# base-32-bit.net
KiCad netlist of a schematic drawn in Altium Designer
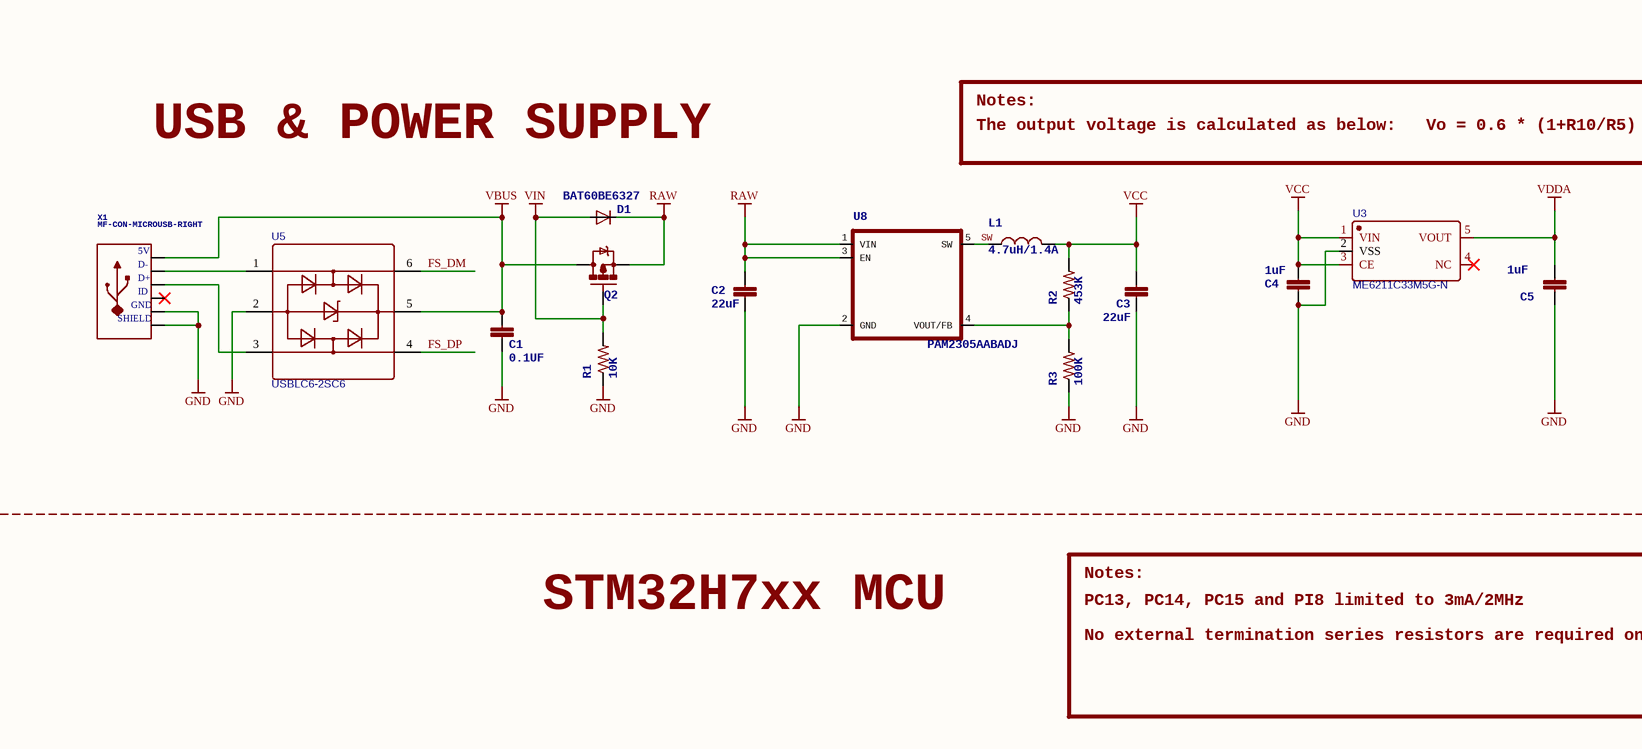
[diagram p0: base-32-bit.SchDoc, top left]
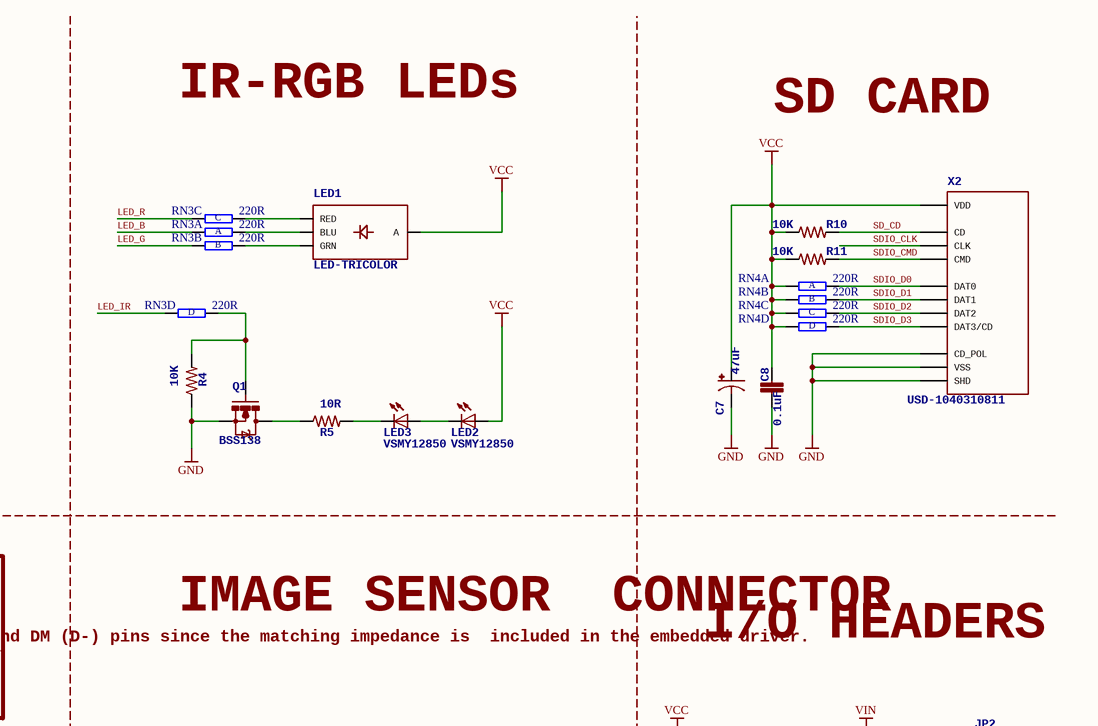
[diagram p1: base-32-bit.SchDoc, top right]
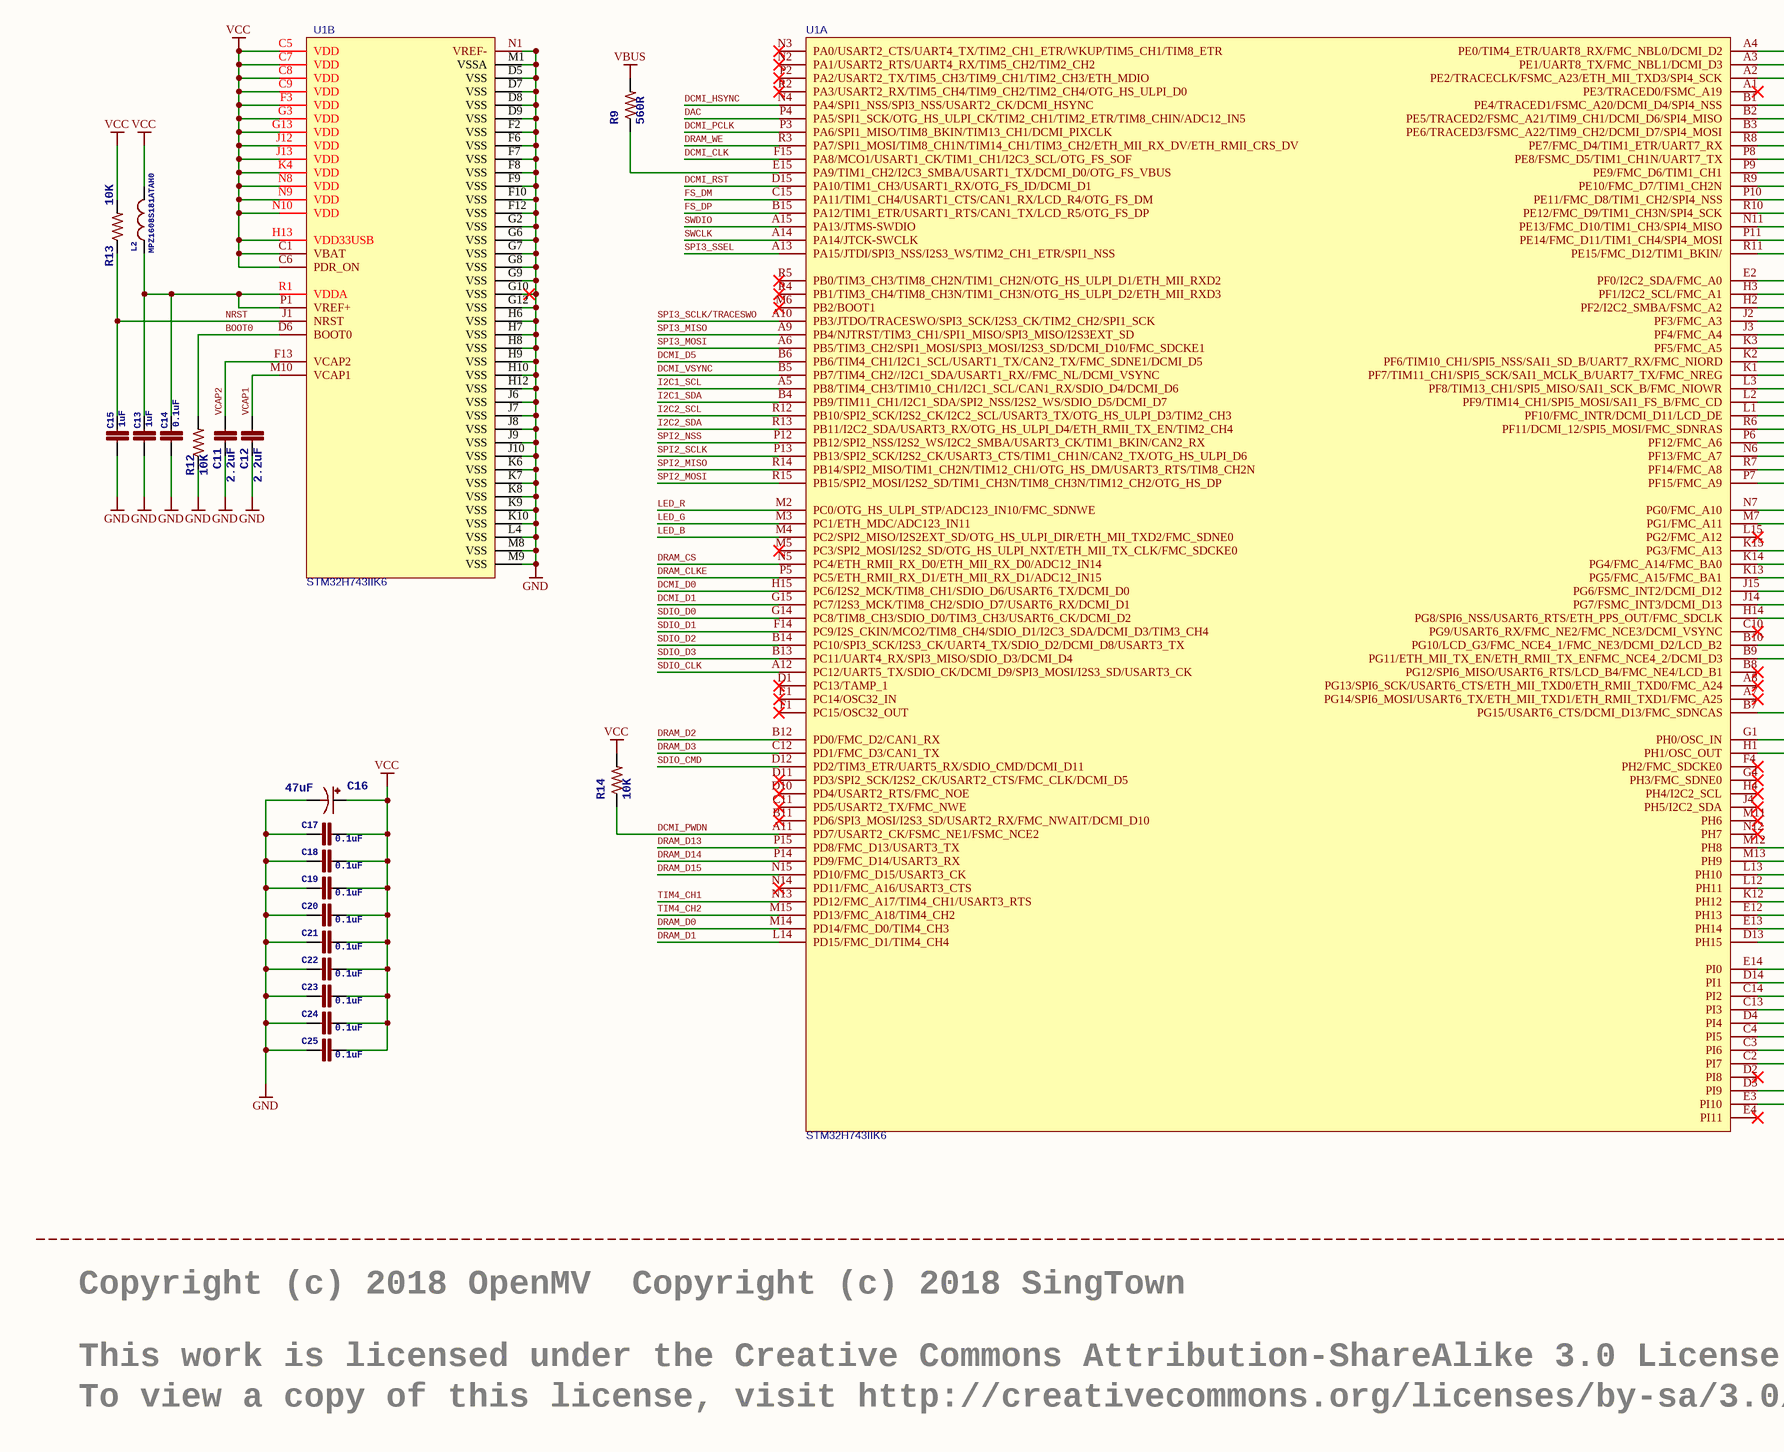
[diagram p2: base-32-bit.SchDoc, bottom left]
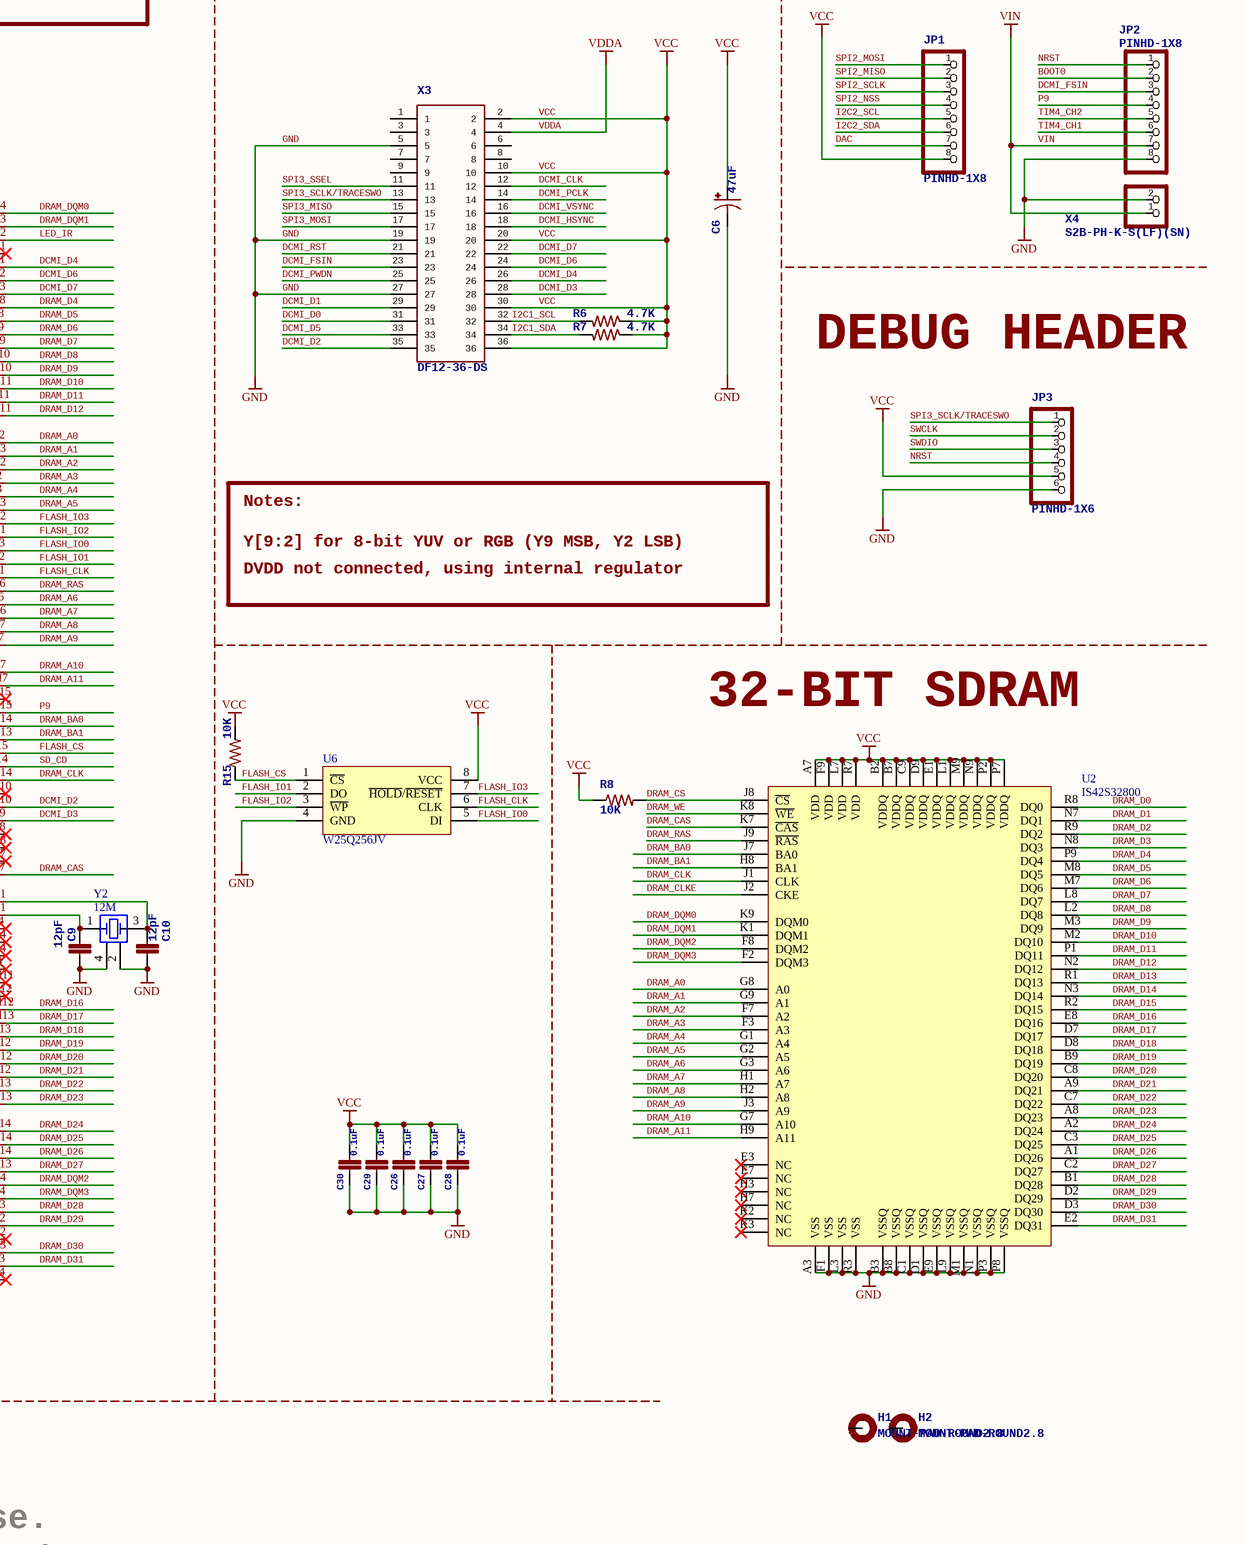
[diagram p3: base-32-bit.SchDoc, bottom right]

(export (version "E")
  (design (tool "Eeschema 10.0.6"))
  (components
    (comp (ref "C1")
      (value "0.1UF")
      (footprint "C0603")
      (description "CapacitorStandard 0603 ceramic capacitor, and 0.1\" leaded capacitor.")
      (libsource (lib "sfe") (part "CAP0805"))
    )
    (comp (ref "C2")
      (value "22uF")
      (footprint "0805")
      (description "CapacitorStandard 0603 ceramic capacitor, and 0.1\" leaded capacitor.")
      (libsource (lib "sfe") (part "CAP0805"))
    )
    (comp (ref "C3")
      (value "22uF")
      (footprint "0805")
      (description "CapacitorStandard 0603 ceramic capacitor, and 0.1\" leaded capacitor.")
      (libsource (lib "sfe") (part "CAP0805"))
    )
    (comp (ref "C4")
      (value "1uF")
      (footprint "0805")
      (description "CapacitorStandard 0603 ceramic capacitor, and 0.1\" leaded capacitor.")
      (libsource (lib "sfe") (part "CAP0805"))
    )
    (comp (ref "C5")
      (value "1uF")
      (footprint "0805")
      (description "CapacitorStandard 0603 ceramic capacitor, and 0.1\" leaded capacitor.")
      (libsource (lib "sfe") (part "CAP0805"))
    )
    (comp (ref "C6") (value "47uF") (footprint "EIA3216") (libsource (lib "sfe") (part "CAP_POL1206")))
    (comp (ref "C7") (value "47uF") (footprint "EIA3216") (libsource (lib "sfe") (part "CAP_POL1206")))
    (comp (ref "C8")
      (value "0.1uF")
      (footprint "0603-CAP")
      (description "CapacitorStandard 0603 ceramic capacitor, and 0.1\" leaded capacitor.")
      (libsource (lib "") (part "CAP0603-CAP_1"))
    )
    (comp (ref "C9")
      (value "12pF")
      (footprint "0603-CAP")
      (description "CapacitorStandard 0603 ceramic capacitor, and 0.1\" leaded capacitor.")
      (libsource (lib "sfe") (part "CAP0603-CAP"))
    )
    (comp (ref "C10")
      (value "12pF")
      (footprint "0603-CAP")
      (description "CapacitorStandard 0603 ceramic capacitor, and 0.1\" leaded capacitor.")
      (libsource (lib "sfe") (part "CAP0603-CAP"))
    )
    (comp (ref "C11")
      (value "2.2uF")
      (footprint "C0402")
      (description "CapacitorStandard 0603 ceramic capacitor, and 0.1\" leaded capacitor.")
      (libsource (lib "") (part "CAP0603-CAP_1"))
    )
    (comp (ref "C12")
      (value "2.2uF")
      (footprint "C0402")
      (description "CapacitorStandard 0603 ceramic capacitor, and 0.1\" leaded capacitor.")
      (libsource (lib "") (part "CAP0603-CAP_1"))
    )
    (comp (ref "C13")
      (value "1uF")
      (footprint "C0402")
      (description "CapacitorStandard 0603 ceramic capacitor, and 0.1\" leaded capacitor.")
      (libsource (lib "") (part "CAP0402-CAP_1"))
    )
    (comp (ref "C14")
      (value "0.1uF")
      (footprint "C0402")
      (description "CapacitorStandard 0603 ceramic capacitor, and 0.1\" leaded capacitor.")
      (libsource (lib "") (part "CAP0402-CAP_1"))
    )
    (comp (ref "C15")
      (value "1uF")
      (footprint "C0402")
      (description "CapacitorStandard 0603 ceramic capacitor, and 0.1\" leaded capacitor.")
      (libsource (lib "") (part "CAP0402-CAP_1"))
    )
    (comp (ref "C16") (value "47uF") (footprint "EIA3216") (libsource (lib "") (part "CAP_POL1206_1")))
    (comp (ref "C17")
      (value "0.1uF")
      (footprint "C0402")
      (description "CapacitorStandard 0603 ceramic capacitor, and 0.1\" leaded capacitor.")
      (libsource (lib "sfe") (part "CAP0402-CAP"))
    )
    (comp (ref "C18")
      (value "0.1uF")
      (footprint "C0402")
      (description "CapacitorStandard 0603 ceramic capacitor, and 0.1\" leaded capacitor.")
      (libsource (lib "sfe") (part "CAP0402-CAP"))
    )
    (comp (ref "C19")
      (value "0.1uF")
      (footprint "C0402")
      (description "CapacitorStandard 0603 ceramic capacitor, and 0.1\" leaded capacitor.")
      (libsource (lib "sfe") (part "CAP0402-CAP"))
    )
    (comp (ref "C20")
      (value "0.1uF")
      (footprint "C0402")
      (description "CapacitorStandard 0603 ceramic capacitor, and 0.1\" leaded capacitor.")
      (libsource (lib "sfe") (part "CAP0402-CAP"))
    )
    (comp (ref "C21")
      (value "0.1uF")
      (footprint "C0402")
      (description "CapacitorStandard 0603 ceramic capacitor, and 0.1\" leaded capacitor.")
      (libsource (lib "sfe") (part "CAP0402-CAP"))
    )
    (comp (ref "C22")
      (value "0.1uF")
      (footprint "C0402")
      (description "CapacitorStandard 0603 ceramic capacitor, and 0.1\" leaded capacitor.")
      (libsource (lib "sfe") (part "CAP0402-CAP"))
    )
    (comp (ref "C23")
      (value "0.1uF")
      (footprint "C0402")
      (description "CapacitorStandard 0603 ceramic capacitor, and 0.1\" leaded capacitor.")
      (libsource (lib "sfe") (part "CAP0402-CAP"))
    )
    (comp (ref "C24")
      (value "0.1uF")
      (footprint "C0402")
      (description "CapacitorStandard 0603 ceramic capacitor, and 0.1\" leaded capacitor.")
      (libsource (lib "sfe") (part "CAP0402-CAP"))
    )
    (comp (ref "C25")
      (value "0.1uF")
      (footprint "C0402")
      (description "CapacitorStandard 0603 ceramic capacitor, and 0.1\" leaded capacitor.")
      (libsource (lib "sfe") (part "CAP0402-CAP"))
    )
    (comp (ref "C26")
      (value "0.1uF")
      (footprint "C0402")
      (description "CapacitorStandard 0603 ceramic capacitor, and 0.1\" leaded capacitor.")
      (libsource (lib "") (part "CAP0402-CAP_1"))
    )
    (comp (ref "C27")
      (value "0.1uF")
      (footprint "C0402")
      (description "CapacitorStandard 0603 ceramic capacitor, and 0.1\" leaded capacitor.")
      (libsource (lib "") (part "CAP0402-CAP_1"))
    )
    (comp (ref "C28")
      (value "0.1uF")
      (footprint "C0402")
      (description "CapacitorStandard 0603 ceramic capacitor, and 0.1\" leaded capacitor.")
      (libsource (lib "") (part "CAP0402-CAP_1"))
    )
    (comp (ref "C29")
      (value "0.1uF")
      (footprint "C0402")
      (description "CapacitorStandard 0603 ceramic capacitor, and 0.1\" leaded capacitor.")
      (libsource (lib "") (part "CAP0402-CAP_1"))
    )
    (comp (ref "C30")
      (value "0.1uF")
      (footprint "C0402")
      (description "CapacitorStandard 0603 ceramic capacitor, and 0.1\" leaded capacitor.")
      (libsource (lib "") (part "CAP0402-CAP_1"))
    )
    (comp (ref "D1") (value "BAT60BE6327") (footprint "SOD-323") (libsource (lib "sfe") (part "DIODESOD")))
    (comp (ref "H1")
      (value "MOUNT-PAD-ROUND2.8")
      (footprint "2,8-PAD")
      (description "MOUNTING PAD, round")
      (libsource (lib "holes") (part "MOUNT-PAD-ROUND2.8"))
    )
    (comp (ref "H2")
      (value "MOUNT-PAD-ROUND2.8")
      (footprint "2,8-PAD")
      (description "MOUNTING PAD, round")
      (libsource (lib "holes") (part "MOUNT-PAD-ROUND2.8"))
    )
    (comp (ref "JP1")
      (value "PINHD-1X8")
      (footprint "1X08")
      (description "PIN HEADER")
      (libsource (lib "pinhead") (part "PINHD-1X8"))
    )
    (comp (ref "JP2")
      (value "PINHD-1X8")
      (footprint "1X08")
      (description "PIN HEADER")
      (libsource (lib "pinhead") (part "PINHD-1X8"))
    )
    (comp (ref "JP3")
      (value "PINHD-1X6")
      (footprint "1X06")
      (description "PIN HEADER")
      (libsource (lib "pinhead") (part "PINHD-1X6"))
    )
    (comp (ref "L1") (value "4.7uH/1.4A") (footprint "1007") (libsource (lib "sfe") (part "INDUCTOR1007")))
    (comp (ref "L2")
      (value "MPZ1608S181ATAH0")
      (footprint "0603")
      (libsource (lib "sfe") (part "INDUCTOR0603"))
    )
    (comp (ref "LED1")
      (value "LED-TRICOLOR")
      (footprint "LED-TRICOLOR-SMD")
      (libsource (lib "sfe") (part "LED-TRICOLOR"))
    )
    (comp (ref "LED2") (value "VSMY12850") (footprint "LED-1206") (libsource (lib "sfe") (part "LED1206")))
    (comp (ref "LED3") (value "VSMY12850") (footprint "LED-1206") (libsource (lib "sfe") (part "LED1206")))
    (comp (ref "Q1")
      (value "BSS138")
      (footprint "SOT23-3")
      (libsource (lib "sfe") (part "MOSFET-NCHANNELSMD"))
    )
    (comp (ref "Q2")
      (value "Si2301BDS")
      (footprint "SOT23-3")
      (libsource (lib "sfe") (part "MOSFET-PCHANNELSMD"))
    )
    (comp (ref "R1")
      (value "10K")
      (footprint "R0603")
      (description "ResistorBasic schematic elements and footprints for 0603, 1206, and PTH resistors.")
      (libsource (lib "sfe") (part "RESISTOR0603-RES"))
    )
    (comp (ref "R2")
      (value "453K")
      (footprint "R0603")
      (description "ResistorBasic schematic elements and footprints for 0603, 1206, and PTH resistors.")
      (libsource (lib "sfe") (part "RESISTOR0603-RES"))
    )
    (comp (ref "R3")
      (value "100K")
      (footprint "R0603")
      (description "ResistorBasic schematic elements and footprints for 0603, 1206, and PTH resistors.")
      (libsource (lib "sfe") (part "RESISTOR0603-RES"))
    )
    (comp (ref "R4")
      (value "10K")
      (footprint "R0603")
      (description "ResistorBasic schematic elements and footprints for 0603, 1206, and PTH resistors.")
      (libsource (lib "sfe") (part "RESISTOR0603-RES"))
    )
    (comp (ref "R5")
      (value "10R")
      (footprint "R0603")
      (description "ResistorBasic schematic elements and footprints for 0603, 1206, and PTH resistors.")
      (libsource (lib "sfe") (part "RESISTOR0603-RES"))
    )
    (comp (ref "R6")
      (value "4.7K")
      (footprint "R0603")
      (description "ResistorBasic schematic elements and footprints for 0603, 1206, and PTH resistors.")
      (libsource (lib "sfe") (part "RESISTOR0603-RES"))
    )
    (comp (ref "R7")
      (value "4.7K")
      (footprint "R0603")
      (description "ResistorBasic schematic elements and footprints for 0603, 1206, and PTH resistors.")
      (libsource (lib "sfe") (part "RESISTOR0603-RES"))
    )
    (comp (ref "R8")
      (value "10K")
      (footprint "R0402")
      (description "ResistorBasic schematic elements and footprints for 0603, 1206, and PTH resistors.")
      (libsource (lib "sfe") (part "RESISTOR0402-RES"))
    )
    (comp (ref "R9")
      (value "560R")
      (footprint "R0603")
      (description "ResistorBasic schematic elements and footprints for 0603, 1206, and PTH resistors.")
      (libsource (lib "sfe") (part "RESISTOR0603-RES"))
    )
    (comp (ref "R10")
      (value "10K")
      (footprint "R0603")
      (description "ResistorBasic schematic elements and footprints for 0603, 1206, and PTH resistors.")
      (libsource (lib "sfe") (part "RESISTOR0603-RES"))
    )
    (comp (ref "R11")
      (value "10K")
      (footprint "R0603")
      (description "ResistorBasic schematic elements and footprints for 0603, 1206, and PTH resistors.")
      (libsource (lib "sfe") (part "RESISTOR0603-RES"))
    )
    (comp (ref "R12")
      (value "10K")
      (footprint "R0603")
      (description "ResistorBasic schematic elements and footprints for 0603, 1206, and PTH resistors.")
      (libsource (lib "sfe") (part "RESISTOR0603-RES"))
    )
    (comp (ref "R13")
      (value "10K")
      (footprint "R0402")
      (description "ResistorBasic schematic elements and footprints for 0603, 1206, and PTH resistors.")
      (libsource (lib "sfe") (part "RESISTOR0603-RES"))
    )
    (comp (ref "R14")
      (value "10K")
      (footprint "R0603")
      (description "ResistorBasic schematic elements and footprints for 0603, 1206, and PTH resistors.")
      (libsource (lib "sfe") (part "RESISTOR0603-RES"))
    )
    (comp (ref "R15")
      (value "10K")
      (footprint "R0603")
      (description "ResistorBasic schematic elements and footprints for 0603, 1206, and PTH resistors.")
      (libsource (lib "sfe") (part "RESISTOR0402-RES"))
    )
    (comp (ref "RN3")
      (value "220R")
      (footprint "RCA-8P4R-0402")
      (libsource (lib "Integrated_Library1") (part "排阻_4P"))
    )
    (comp (ref "RN4")
      (value "220R")
      (footprint "RCA-8P4R-0402")
      (libsource (lib "Integrated_Library1") (part "排阻_4P"))
    )
    (comp (ref "U1")
      (value "STM32H743IIK6")
      (footprint "UFBGA-201_L10.0-W10.0-P0.65-TL_STM32H743IIK6")
      (fields
        (field (name "BOM_SUPPLIER PART") "C129442")
        (field (name "SUBPART_NO") "2")
        (field (name "CONTRIBUTOR") "LCSC")
      )
      (libsource (lib "Integrated_Library1") (part "STM32H743IIK6"))
    )
    (comp (ref "U2")
      (value "IS42S32800")
      (footprint "BGA-90-8000X13000DE")
      (libsource (lib "Schlib1") (part "IS42S32800"))
    )
    (comp (ref "U3")
      (value "ME6211C33M5G-N")
      (footprint "SOT-23-5")
      (fields (field (name "BOM_SUPPLIER PART") "C82942"))
      (libsource (lib "Integrated_Library1") (part "ME6211C33M5G-N"))
    )
    (comp (ref "U5")
      (value "USBLC6-2SC6")
      (footprint "SOT-23-6")
      (fields (field (name "BOM_SUPPLIER PART") "C7519"))
      (libsource (lib "Integrated_Library1") (part "USBLC6-2SC6"))
    )
    (comp (ref "U6")
      (value "W25Q256JV")
      (footprint "WSON-8_L8.0-W6.10-P1.27-BL-EP")
      (libsource (lib "Integrated_Library1") (part "W25Q128JVSQ"))
    )
    (comp (ref "U8")
      (value "PAM2305AABADJ")
      (footprint "TSOT25")
      (libsource (lib "regulators") (part "PAM2305AAB330"))
    )
    (comp (ref "X1")
      (value "MF-CON-MICROUSB-RIGHT")
      (footprint "MICROUSB-RIGHT")
      (libsource (lib "base-16-bit") (part "USB_MICRO_RIGHT"))
    )
    (comp (ref "X2")
      (value "USD-1040310811")
      (footprint "1040310811")
      (libsource (lib "base-16-bit") (part "USD-1040310811"))
    )
    (comp (ref "X3")
      (value "DF12-36-DS")
      (footprint "DF12-36-DS")
      (libsource (lib "DF12") (part "DF12-36-DS"))
    )
    (comp (ref "X4")
      (value "S2B-PH-K-S(LF)(SN)")
      (footprint "JST-PH-2-THM-RA")
      (libsource (lib "adafruit-updated") (part "JST_2PIN-THM-RA"))
    )
    (comp (ref "Y2")
      (value "12M")
      (footprint "OSC-SMD_4P-L2.5-W2.0-BL")
      (libsource (lib "wwwmcucn_sch") (part "XTAL-NV-4"))
    )
  )
  (nets
    (net (code "1") (name "/BOOT0") (class "Default")
      (node (ref "JP2") (pin "2") (pinfunction "2_2") (pintype "passive"))
      (node (ref "R12") (pin "2") (pinfunction "2_2") (pintype "passive"))
      (node (ref "U1") (pin "D6") (pinfunction "BOOT0_D6") (pintype "passive"))
    )
    (net (code "2") (name "/DAC") (class "Default")
      (node (ref "JP1") (pin "7") (pinfunction "7_7") (pintype "passive"))
      (node (ref "U1") (pin "P4") (pinfunction "PA5/SPI1_SCK/OTG_HS_ULPI_CK/TIM2_CH1/TIM2_ETR/TIM8_CHIN/ADC12_IN5_P4") (pintype "passive"))
    )
    (net (code "3") (name "/DCMI_CLK") (class "Default")
      (node (ref "U1") (pin "F15") (pinfunction "PA8/MCO1/USART1_CK/TIM1_CH1/I2C3_SCL/OTG_FS_SOF_F15") (pintype "passive"))
      (node (ref "X3") (pin "12") (pinfunction "12_12") (pintype "passive"))
    )
    (net (code "4") (name "/DCMI_D0") (class "Default")
      (node (ref "U1") (pin "H15") (pinfunction "PC6/I2S2_MCK/TIM8_CH1/SDIO_D6/USART6_TX/DCMI_D0_H15") (pintype "passive"))
      (node (ref "X3") (pin "31") (pinfunction "31_31") (pintype "passive"))
    )
    (net (code "5") (name "/DCMI_D1") (class "Default")
      (node (ref "U1") (pin "G15") (pinfunction "PC7/I2S3_MCK/TIM8_CH2/SDIO_D7/USART6_RX/DCMI_D1_G15") (pintype "passive"))
      (node (ref "X3") (pin "29") (pinfunction "29_29") (pintype "passive"))
    )
    (net (code "6") (name "/DCMI_D2") (class "Default")
      (node (ref "U1") (pin "B10") (pinfunction "PG10/LCD_G3/FMC_NCE4_1/FMC_NE3/DCMI_D2/LCD_B2_B10") (pintype "passive"))
      (node (ref "X3") (pin "35") (pinfunction "35_35") (pintype "passive"))
    )
    (net (code "7") (name "/DCMI_D3") (class "Default")
      (node (ref "U1") (pin "B9") (pinfunction "PG11/ETH_MII_TX_EN/ETH_RMII_TX_ENFMC_NCE4_2/DCMI_D3_B9") (pintype "passive"))
      (node (ref "X3") (pin "28") (pinfunction "28_28") (pintype "passive"))
    )
    (net (code "8") (name "/DCMI_D4") (class "Default")
      (node (ref "U1") (pin "B1") (pinfunction "PE4/TRACED1/FSMC_A20/DCMI_D4/SPI4_NSS_B1") (pintype "passive"))
      (node (ref "X3") (pin "26") (pinfunction "26_26") (pintype "passive"))
    )
    (net (code "9") (name "/DCMI_D5") (class "Default")
      (node (ref "U1") (pin "B6") (pinfunction "PB6/TIM4_CH1/I2C1_SCL/USART1_TX/CAN2_TX/FMC_SDNE1/DCMI_D5_B6") (pintype "passive"))
      (node (ref "X3") (pin "33") (pinfunction "33_33") (pintype "passive"))
    )
    (net (code "10") (name "/DCMI_D6") (class "Default")
      (node (ref "U1") (pin "B2") (pinfunction "PE5/TRACED2/FSMC_A21/TIM9_CH1/DCMI_D6/SPI4_MISO_B2") (pintype "passive"))
      (node (ref "X3") (pin "24") (pinfunction "24_24") (pintype "passive"))
    )
    (net (code "11") (name "/DCMI_D7") (class "Default")
      (node (ref "U1") (pin "B3") (pinfunction "PE6/TRACED3/FSMC_A22/TIM9_CH2/DCMI_D7/SPI4_MOSI_B3") (pintype "passive"))
      (node (ref "X3") (pin "22") (pinfunction "22_22") (pintype "passive"))
    )
    (net (code "12") (name "/DCMI_FSIN") (class "Default")
      (node (ref "JP2") (pin "3") (pinfunction "3_3") (pintype "passive"))
      (node (ref "X3") (pin "23") (pinfunction "23_23") (pintype "passive"))
    )
    (net (code "13") (name "/DCMI_HSYNC") (class "Default")
      (node (ref "U1") (pin "N4") (pinfunction "PA4/SPI1_NSS/SPI3_NSS/USART2_CK/DCMI_HSYNC_N4") (pintype "passive"))
      (node (ref "X3") (pin "18") (pinfunction "18_18") (pintype "passive"))
    )
    (net (code "14") (name "/DCMI_PCLK") (class "Default")
      (node (ref "U1") (pin "P3") (pinfunction "PA6/SPI1_MISO/TIM8_BKIN/TIM13_CH1/DCMI_PIXCLK_P3") (pintype "passive"))
      (node (ref "X3") (pin "14") (pinfunction "14_14") (pintype "passive"))
    )
    (net (code "15") (name "/DCMI_PWDN") (class "Default")
      (node (ref "R14") (pin "1") (pinfunction "1_1") (pintype "passive"))
      (node (ref "U1") (pin "A11") (pinfunction "PD7/USART2_CK/FSMC_NE1/FSMC_NCE2_A11") (pintype "passive"))
      (node (ref "X3") (pin "25") (pinfunction "25_25") (pintype "passive"))
    )
    (net (code "16") (name "/DCMI_RST") (class "Default")
      (node (ref "U1") (pin "D15") (pinfunction "PA10/TIM1_CH3/USART1_RX/OTG_FS_ID/DCMI_D1_D15") (pintype "passive"))
      (node (ref "X3") (pin "21") (pinfunction "21_21") (pintype "passive"))
    )
    (net (code "17") (name "/DCMI_VSYNC") (class "Default")
      (node (ref "U1") (pin "B5") (pinfunction "PB7/TIM4_CH2//I2C1_SDA/USART1_RX//FMC_NL/DCMI_VSYNC_B5") (pintype "passive"))
      (node (ref "X3") (pin "16") (pinfunction "16_16") (pintype "passive"))
    )
    (net (code "18") (name "/DRAM_A0") (class "Default")
      (node (ref "U1") (pin "E2") (pinfunction "PF0/I2C2_SDA/FMC_A0_E2") (pintype "passive"))
      (node (ref "U2") (pin "G8") (pinfunction "A0_G8") (pintype "passive"))
    )
    (net (code "19") (name "/DRAM_A1") (class "Default")
      (node (ref "U1") (pin "H3") (pinfunction "PF1/I2C2_SCL/FMC_A1_H3") (pintype "passive"))
      (node (ref "U2") (pin "G9") (pinfunction "A1_G9") (pintype "passive"))
    )
    (net (code "20") (name "/DRAM_A2") (class "Default")
      (node (ref "U1") (pin "H2") (pinfunction "PF2/I2C2_SMBA/FSMC_A2_H2") (pintype "passive"))
      (node (ref "U2") (pin "F7") (pinfunction "A2_F7") (pintype "passive"))
    )
    (net (code "21") (name "/DRAM_A3") (class "Default")
      (node (ref "U1") (pin "J2") (pinfunction "PF3/FMC_A3_J2") (pintype "passive"))
      (node (ref "U2") (pin "F3") (pinfunction "A3_F3") (pintype "passive"))
    )
    (net (code "22") (name "/DRAM_A4") (class "Default")
      (node (ref "U1") (pin "J3") (pinfunction "PF4/FMC_A4_J3") (pintype "passive"))
      (node (ref "U2") (pin "G1") (pinfunction "A4_G1") (pintype "passive"))
    )
    (net (code "23") (name "/DRAM_A5") (class "Default")
      (node (ref "U1") (pin "K3") (pinfunction "PF5/FMC_A5_K3") (pintype "passive"))
      (node (ref "U2") (pin "G2") (pinfunction "A5_G2") (pintype "passive"))
    )
    (net (code "24") (name "/DRAM_A6") (class "Default")
      (node (ref "U1") (pin "P6") (pinfunction "PF12/FMC_A6_P6") (pintype "passive"))
      (node (ref "U2") (pin "G3") (pinfunction "A6_G3") (pintype "passive"))
    )
    (net (code "25") (name "/DRAM_A7") (class "Default")
      (node (ref "U1") (pin "N6") (pinfunction "PF13/FMC_A7_N6") (pintype "passive"))
      (node (ref "U2") (pin "H1") (pinfunction "A7_H1") (pintype "passive"))
    )
    (net (code "26") (name "/DRAM_A8") (class "Default")
      (node (ref "U1") (pin "R7") (pinfunction "PF14/FMC_A8_R7") (pintype "passive"))
      (node (ref "U2") (pin "H2") (pinfunction "A8_H2") (pintype "passive"))
    )
    (net (code "27") (name "/DRAM_A9") (class "Default")
      (node (ref "U1") (pin "P7") (pinfunction "PF15/FMC_A9_P7") (pintype "passive"))
      (node (ref "U2") (pin "J3") (pinfunction "A9_J3") (pintype "passive"))
    )
    (net (code "28") (name "/DRAM_A10") (class "Default")
      (node (ref "U1") (pin "N7") (pinfunction "PG0/FMC_A10_N7") (pintype "passive"))
      (node (ref "U2") (pin "G7") (pinfunction "A10_G7") (pintype "passive"))
    )
    (net (code "29") (name "/DRAM_A11") (class "Default")
      (node (ref "U1") (pin "M7") (pinfunction "PG1/FMC_A11_M7") (pintype "passive"))
      (node (ref "U2") (pin "H9") (pinfunction "A11_H9") (pintype "passive"))
    )
    (net (code "30") (name "/DRAM_BA0") (class "Default")
      (node (ref "U1") (pin "K14") (pinfunction "PG4/FMC_A14/FMC_BA0_K14") (pintype "passive"))
      (node (ref "U2") (pin "J7") (pinfunction "BA0_J7") (pintype "passive"))
    )
    (net (code "31") (name "/DRAM_BA1") (class "Default")
      (node (ref "U1") (pin "K13") (pinfunction "PG5/FMC_A15/FMC_BA1_K13") (pintype "passive"))
      (node (ref "U2") (pin "H8") (pinfunction "BA1_H8") (pintype "passive"))
    )
    (net (code "32") (name "/DRAM_CAS") (class "Default")
      (node (ref "U1") (pin "B7") (pinfunction "PG15/USART6_CTS/DCMI_D13/FMC_SDNCAS_B7") (pintype "passive"))
      (node (ref "U2") (pin "K7") (pinfunction "~{CAS}_K7") (pintype "passive"))
    )
    (net (code "33") (name "/DRAM_CLK") (class "Default")
      (node (ref "U1") (pin "H14") (pinfunction "PG8/SPI6_NSS/USART6_RTS/ETH_PPS_OUT/FMC_SDCLK_H14") (pintype "passive"))
      (node (ref "U2") (pin "J1") (pinfunction "CLK_J1") (pintype "passive"))
    )
    (net (code "34") (name "/DRAM_CLKE") (class "Default")
      (node (ref "U1") (pin "P5") (pinfunction "PC5/ETH_RMII_RX_D1/ETH_MII_RX_D1/ADC12_IN15_P5") (pintype "passive"))
      (node (ref "U2") (pin "J2") (pinfunction "CKE_J2") (pintype "passive"))
    )
    (net (code "35") (name "/DRAM_CS") (class "Default")
      (node (ref "R8") (pin "2") (pinfunction "2_2") (pintype "passive"))
      (node (ref "U1") (pin "N5") (pinfunction "PC4/ETH_RMII_RX_D0/ETH_MII_RX_D0/ADC12_IN14_N5") (pintype "passive"))
      (node (ref "U2") (pin "J8") (pinfunction "~{CS}_J8") (pintype "passive"))
    )
    (net (code "36") (name "/DRAM_D0") (class "Default")
      (node (ref "U1") (pin "M14") (pinfunction "PD14/FMC_D0/TIM4_CH3_M14") (pintype "passive"))
      (node (ref "U2") (pin "R8") (pinfunction "DQ0_R8") (pintype "passive"))
    )
    (net (code "37") (name "/DRAM_D1") (class "Default")
      (node (ref "U1") (pin "L14") (pinfunction "PD15/FMC_D1/TIM4_CH4_L14") (pintype "passive"))
      (node (ref "U2") (pin "N7") (pinfunction "DQ1_N7") (pintype "passive"))
    )
    (net (code "38") (name "/DRAM_D2") (class "Default")
      (node (ref "U1") (pin "B12") (pinfunction "PD0/FMC_D2/CAN1_RX_B12") (pintype "passive"))
      (node (ref "U2") (pin "R9") (pinfunction "DQ2_R9") (pintype "passive"))
    )
    (net (code "39") (name "/DRAM_D3") (class "Default")
      (node (ref "U1") (pin "C12") (pinfunction "PD1/FMC_D3/CAN1_TX_C12") (pintype "passive"))
      (node (ref "U2") (pin "N8") (pinfunction "DQ3_N8") (pintype "passive"))
    )
    (net (code "40") (name "/DRAM_D4") (class "Default")
      (node (ref "U1") (pin "R8") (pinfunction "PE7/FMC_D4/TIM1_ETR/UART7_RX_R8") (pintype "passive"))
      (node (ref "U2") (pin "P9") (pinfunction "DQ4_P9") (pintype "passive"))
    )
    (net (code "41") (name "/DRAM_D5") (class "Default")
      (node (ref "U1") (pin "P8") (pinfunction "PE8/FSMC_D5/TIM1_CH1N/UART7_TX_P8") (pintype "passive"))
      (node (ref "U2") (pin "M8") (pinfunction "DQ5_M8") (pintype "passive"))
    )
    (net (code "42") (name "/DRAM_D6") (class "Default")
      (node (ref "U1") (pin "P9") (pinfunction "PE9/FMC_D6/TIM1_CH1_P9") (pintype "passive"))
      (node (ref "U2") (pin "M7") (pinfunction "DQ6_M7") (pintype "passive"))
    )
    (net (code "43") (name "/DRAM_D7") (class "Default")
      (node (ref "U1") (pin "R9") (pinfunction "PE10/FMC_D7/TIM1_CH2N_R9") (pintype "passive"))
      (node (ref "U2") (pin "L8") (pinfunction "DQ7_L8") (pintype "passive"))
    )
    (net (code "44") (name "/DRAM_D8") (class "Default")
      (node (ref "U1") (pin "P10") (pinfunction "PE11/FMC_D8/TIM1_CH2/SPI4_NSS_P10") (pintype "passive"))
      (node (ref "U2") (pin "L2") (pinfunction "DQ8_L2") (pintype "passive"))
    )
    (net (code "45") (name "/DRAM_D9") (class "Default")
      (node (ref "U1") (pin "R10") (pinfunction "PE12/FMC_D9/TIM1_CH3N/SPI4_SCK_R10") (pintype "passive"))
      (node (ref "U2") (pin "M3") (pinfunction "DQ9_M3") (pintype "passive"))
    )
    (net (code "46") (name "/DRAM_D10") (class "Default")
      (node (ref "U1") (pin "N11") (pinfunction "PE13/FMC_D10/TIM1_CH3/SPI4_MISO_N11") (pintype "passive"))
      (node (ref "U2") (pin "M2") (pinfunction "DQ10_M2") (pintype "passive"))
    )
    (net (code "47") (name "/DRAM_D11") (class "Default")
      (node (ref "U1") (pin "P11") (pinfunction "PE14/FMC_D11/TIM1_CH4/SPI4_MOSI_P11") (pintype "passive"))
      (node (ref "U2") (pin "P1") (pinfunction "DQ11_P1") (pintype "passive"))
    )
    (net (code "48") (name "/DRAM_D12") (class "Default")
      (node (ref "U1") (pin "R11") (pinfunction "PE15/FMC_D12/TIM1_BKIN/_R11") (pintype "passive"))
      (node (ref "U2") (pin "N2") (pinfunction "DQ12_N2") (pintype "passive"))
    )
    (net (code "49") (name "/DRAM_D13") (class "Default")
      (node (ref "U1") (pin "P15") (pinfunction "PD8/FMC_D13/USART3_TX_P15") (pintype "passive"))
      (node (ref "U2") (pin "R1") (pinfunction "DQ13_R1") (pintype "passive"))
    )
    (net (code "50") (name "/DRAM_D14") (class "Default")
      (node (ref "U1") (pin "P14") (pinfunction "PD9/FMC_D14/USART3_RX_P14") (pintype "passive"))
      (node (ref "U2") (pin "N3") (pinfunction "DQ14_N3") (pintype "passive"))
    )
    (net (code "51") (name "/DRAM_D15") (class "Default")
      (node (ref "U1") (pin "N15") (pinfunction "PD10/FMC_D15/USART3_CK_N15") (pintype "passive"))
      (node (ref "U2") (pin "R2") (pinfunction "DQ15_R2") (pintype "passive"))
    )
    (net (code "52") (name "/DRAM_D16") (class "Default")
      (node (ref "U1") (pin "M12") (pinfunction "PH8_M12") (pintype "passive"))
      (node (ref "U2") (pin "E8") (pinfunction "DQ16_E8") (pintype "passive"))
    )
    (net (code "53") (name "/DRAM_D17") (class "Default")
      (node (ref "U1") (pin "M13") (pinfunction "PH9_M13") (pintype "passive"))
      (node (ref "U2") (pin "D7") (pinfunction "DQ17_D7") (pintype "passive"))
    )
    (net (code "54") (name "/DRAM_D18") (class "Default")
      (node (ref "U1") (pin "L13") (pinfunction "PH10_L13") (pintype "passive"))
      (node (ref "U2") (pin "D8") (pinfunction "DQ18_D8") (pintype "passive"))
    )
    (net (code "55") (name "/DRAM_D19") (class "Default")
      (node (ref "U1") (pin "L12") (pinfunction "PH11_L12") (pintype "passive"))
      (node (ref "U2") (pin "B9") (pinfunction "DQ19_B9") (pintype "passive"))
    )
    (net (code "56") (name "/DRAM_D20") (class "Default")
      (node (ref "U1") (pin "K12") (pinfunction "PH12_K12") (pintype "passive"))
      (node (ref "U2") (pin "C8") (pinfunction "DQ20_C8") (pintype "passive"))
    )
    (net (code "57") (name "/DRAM_D21") (class "Default")
      (node (ref "U1") (pin "E12") (pinfunction "PH13_E12") (pintype "passive"))
      (node (ref "U2") (pin "A9") (pinfunction "DQ21_A9") (pintype "passive"))
    )
    (net (code "58") (name "/DRAM_D22") (class "Default")
      (node (ref "U1") (pin "E13") (pinfunction "PH14_E13") (pintype "passive"))
      (node (ref "U2") (pin "C7") (pinfunction "DQ22_C7") (pintype "passive"))
    )
    (net (code "59") (name "/DRAM_D23") (class "Default")
      (node (ref "U1") (pin "D13") (pinfunction "PH15_D13") (pintype "passive"))
      (node (ref "U2") (pin "A8") (pinfunction "DQ23_A8") (pintype "passive"))
    )
    (net (code "60") (name "/DRAM_D24") (class "Default")
      (node (ref "U1") (pin "E14") (pinfunction "PI0_E14") (pintype "passive"))
      (node (ref "U2") (pin "A2") (pinfunction "DQ24_A2") (pintype "passive"))
    )
    (net (code "61") (name "/DRAM_D25") (class "Default")
      (node (ref "U1") (pin "D14") (pinfunction "PI1_D14") (pintype "passive"))
      (node (ref "U2") (pin "C3") (pinfunction "DQ25_C3") (pintype "passive"))
    )
    (net (code "62") (name "/DRAM_D26") (class "Default")
      (node (ref "U1") (pin "C14") (pinfunction "PI2_C14") (pintype "passive"))
      (node (ref "U2") (pin "A1") (pinfunction "DQ26_A1") (pintype "passive"))
    )
    (net (code "63") (name "/DRAM_D27") (class "Default")
      (node (ref "U1") (pin "C13") (pinfunction "PI3_C13") (pintype "passive"))
      (node (ref "U2") (pin "C2") (pinfunction "DQ27_C2") (pintype "passive"))
    )
    (net (code "64") (name "/DRAM_D28") (class "Default")
      (node (ref "U1") (pin "C3") (pinfunction "PI6_C3") (pintype "passive"))
      (node (ref "U2") (pin "B1") (pinfunction "DQ28_B1") (pintype "passive"))
    )
    (net (code "65") (name "/DRAM_D29") (class "Default")
      (node (ref "U1") (pin "C2") (pinfunction "PI7_C2") (pintype "passive"))
      (node (ref "U2") (pin "D2") (pinfunction "DQ29_D2") (pintype "passive"))
    )
    (net (code "66") (name "/DRAM_D30") (class "Default")
      (node (ref "U1") (pin "D3") (pinfunction "PI9_D3") (pintype "passive"))
      (node (ref "U2") (pin "D3") (pinfunction "DQ30_D3") (pintype "passive"))
    )
    (net (code "67") (name "/DRAM_D31") (class "Default")
      (node (ref "U1") (pin "E3") (pinfunction "PI10_E3") (pintype "passive"))
      (node (ref "U2") (pin "E2") (pinfunction "DQ31_E2") (pintype "passive"))
    )
    (net (code "68") (name "/DRAM_DQM0") (class "Default")
      (node (ref "U1") (pin "A4") (pinfunction "PE0/TIM4_ETR/UART8_RX/FMC_NBL0/DCMI_D2_A4") (pintype "passive"))
      (node (ref "U2") (pin "K9") (pinfunction "DQM0_K9") (pintype "passive"))
    )
    (net (code "69") (name "/DRAM_DQM1") (class "Default")
      (node (ref "U1") (pin "A3") (pinfunction "PE1/UART8_TX/FMC_NBL1/DCMI_D3_A3") (pintype "passive"))
      (node (ref "U2") (pin "K1") (pinfunction "DQM1_K1") (pintype "passive"))
    )
    (net (code "70") (name "/DRAM_DQM2") (class "Default")
      (node (ref "U1") (pin "D4") (pinfunction "PI4_D4") (pintype "passive"))
      (node (ref "U2") (pin "F8") (pinfunction "DQM2_F8") (pintype "passive"))
    )
    (net (code "71") (name "/DRAM_DQM3") (class "Default")
      (node (ref "U1") (pin "C4") (pinfunction "PI5_C4") (pintype "passive"))
      (node (ref "U2") (pin "F2") (pinfunction "DQM3_F2") (pintype "passive"))
    )
    (net (code "72") (name "/DRAM_RAS") (class "Default")
      (node (ref "U1") (pin "R6") (pinfunction "PF11/DCMI_12/SPI5_MOSI/FMC_SDNRAS_R6") (pintype "passive"))
      (node (ref "U2") (pin "J9") (pinfunction "~{RAS}_J9") (pintype "passive"))
    )
    (net (code "73") (name "/DRAM_WE") (class "Default")
      (node (ref "U1") (pin "R3") (pinfunction "PA7/SPI1_MOSI/TIM8_CH1N/TIM14_CH1/TIM3_CH2/ETH_MII_RX_DV/ETH_RMII_CRS_DV_R3") (pintype "passive"))
      (node (ref "U2") (pin "K8") (pinfunction "~{WE}_K8") (pintype "passive"))
    )
    (net (code "74") (name "/FLASH_CLK") (class "Default")
      (node (ref "U1") (pin "L1") (pinfunction "PF10/FMC_INTR/DCMI_D11/LCD_DE_L1") (pintype "passive"))
      (node (ref "U6") (pin "6") (pinfunction "CLK_6") (pintype "passive"))
    )
    (net (code "75") (name "/FLASH_CS") (class "Default")
      (node (ref "R15") (pin "1") (pinfunction "1_1") (pintype "passive"))
      (node (ref "U1") (pin "J15") (pinfunction "PG6/FSMC_INT2/DCMI_D12_J15") (pintype "passive"))
      (node (ref "U6") (pin "1") (pinfunction "~{CS}_1") (pintype "passive"))
    )
    (net (code "76") (name "/FLASH_IO0") (class "Default")
      (node (ref "U1") (pin "L3") (pinfunction "PF8/TIM13_CH1/SPI5_MISO/SAI1_SCK_B/FMC_NIOWR_L3") (pintype "passive"))
      (node (ref "U6") (pin "5") (pinfunction "DI_5") (pintype "passive"))
    )
    (net (code "77") (name "/FLASH_IO1") (class "Default")
      (node (ref "U1") (pin "L2") (pinfunction "PF9/TIM14_CH1/SPI5_MOSI/SAI1_FS_B/FMC_CD_L2") (pintype "passive"))
      (node (ref "U6") (pin "2") (pinfunction "DO_2") (pintype "passive"))
    )
    (net (code "78") (name "/FLASH_IO2") (class "Default")
      (node (ref "U1") (pin "K1") (pinfunction "PF7/TIM11_CH1/SPI5_SCK/SAI1_MCLK_B/UART7_TX/FMC_NREG_K1") (pintype "passive"))
      (node (ref "U6") (pin "3") (pinfunction "~{WP}_3") (pintype "passive"))
    )
    (net (code "79") (name "/FLASH_IO3") (class "Default")
      (node (ref "U1") (pin "K2") (pinfunction "PF6/TIM10_CH1/SPI5_NSS/SAI1_SD_B/UART7_RX/FMC_NIORD_K2") (pintype "passive"))
      (node (ref "U6") (pin "7") (pinfunction "~{HOLD}/~{RESET}_7") (pintype "passive"))
    )
    (net (code "80") (name "/FS_DM") (class "Default")
      (node (ref "U1") (pin "C15") (pinfunction "PA11/TIM1_CH4/USART1_CTS/CAN1_RX/LCD_R4/OTG_FS_DM_C15") (pintype "passive"))
      (node (ref "U5") (pin "6") (pinfunction "6_6") (pintype "passive"))
    )
    (net (code "81") (name "/FS_DP") (class "Default")
      (node (ref "U1") (pin "B15") (pinfunction "PA12/TIM1_ETR/USART1_RTS/CAN1_TX/LCD_R5/OTG_FS_DP_B15") (pintype "passive"))
      (node (ref "U5") (pin "4") (pinfunction "4_4") (pintype "passive"))
    )
    (net (code "82") (name "/I2C1_SCL") (class "Default")
      (node (ref "R6") (pin "2") (pinfunction "2_2") (pintype "passive"))
      (node (ref "U1") (pin "A5") (pinfunction "PB8/TIM4_CH3/TIM10_CH1/I2C1_SCL/CAN1_RX/SDIO_D4/DCMI_D6_A5") (pintype "passive"))
      (node (ref "X3") (pin "32") (pinfunction "32_32") (pintype "passive"))
    )
    (net (code "83") (name "/I2C1_SDA") (class "Default")
      (node (ref "R7") (pin "2") (pinfunction "2_2") (pintype "passive"))
      (node (ref "U1") (pin "B4") (pinfunction "PB9/TIM11_CH1/I2C1_SDA/SPI2_NSS/I2S2_WS/SDIO_D5/DCMI_D7_B4") (pintype "passive"))
      (node (ref "X3") (pin "34") (pinfunction "34_34") (pintype "passive"))
    )
    (net (code "84") (name "/I2C2_SCL") (class "Default")
      (node (ref "JP1") (pin "5") (pinfunction "5_5") (pintype "passive"))
      (node (ref "U1") (pin "R12") (pinfunction "PB10/SPI2_SCK/I2S2_CK/I2C2_SCL/USART3_TX/OTG_HS_ULPI_D3/TIM2_CH3_R12") (pintype "passive"))
    )
    (net (code "85") (name "/I2C2_SDA") (class "Default")
      (node (ref "JP1") (pin "6") (pinfunction "6_6") (pintype "passive"))
      (node (ref "U1") (pin "R13") (pinfunction "PB11/I2C2_SDA/USART3_RX/OTG_HS_ULPI_D4/ETH_RMII_TX_EN/TIM2_CH4_R13") (pintype "passive"))
    )
    (net (code "86") (name "/LED_B") (class "Default")
      (node (ref "RN3") (pin "1") (pinfunction "1_1") (pintype "passive"))
      (node (ref "U1") (pin "M4") (pinfunction "PC2/SPI2_MISO/I2S2EXT_SD/OTG_HS_ULPI_DIR/ETH_MII_TXD2/FMC_SDNE0_M4") (pintype "passive"))
    )
    (net (code "87") (name "/LED_G") (class "Default")
      (node (ref "RN3") (pin "2") (pinfunction "2_2") (pintype "passive"))
      (node (ref "U1") (pin "M3") (pinfunction "PC1/ETH_MDC/ADC123_IN11_M3") (pintype "passive"))
    )
    (net (code "88") (name "/LED_IR") (class "Default")
      (node (ref "RN3") (pin "4") (pinfunction "4_4") (pintype "passive"))
      (node (ref "U1") (pin "A2") (pinfunction "PE2/TRACECLK/FSMC_A23/ETH_MII_TXD3/SPI4_SCK_A2") (pintype "passive"))
    )
    (net (code "89") (name "/LED_R") (class "Default")
      (node (ref "RN3") (pin "3") (pinfunction "3_3") (pintype "passive"))
      (node (ref "U1") (pin "M2") (pinfunction "PC0/OTG_HS_ULPI_STP/ADC123_IN10/FMC_SDNWE_M2") (pintype "passive"))
    )
    (net (code "90") (name "/NRST") (class "Default")
      (node (ref "C15") (pin "1") (pinfunction "1_1") (pintype "passive"))
      (node (ref "JP2") (pin "1") (pinfunction "1_1") (pintype "passive"))
      (node (ref "JP3") (pin "4") (pinfunction "4_4") (pintype "passive"))
      (node (ref "R13") (pin "1") (pinfunction "1_1") (pintype "passive"))
      (node (ref "U1") (pin "J1") (pinfunction "NRST_J1") (pintype "passive"))
    )
    (net (code "91") (name "/P9") (class "Default")
      (node (ref "JP2") (pin "4") (pinfunction "4_4") (pintype "passive"))
      (node (ref "U1") (pin "K15") (pinfunction "PG3/FMC_A13_K15") (pintype "passive"))
    )
    (net (code "92") (name "/SDIO_CLK") (class "Default")
      (node (ref "U1") (pin "A12") (pinfunction "PC12/UART5_TX/SDIO_CK/DCMI_D9/SPI3_MOSI/I2S3_SD/USART3_CK_A12") (pintype "passive"))
      (node (ref "X2") (pin "P$5") (pinfunction "CLK_P$5") (pintype "passive"))
    )
    (net (code "93") (name "/SDIO_CMD") (class "Default")
      (node (ref "R11") (pin "2") (pinfunction "2_2") (pintype "passive"))
      (node (ref "U1") (pin "D12") (pinfunction "PD2/TIM3_ETR/UART5_RX/SDIO_CMD/DCMI_D11_D12") (pintype "passive"))
      (node (ref "X2") (pin "P$3") (pinfunction "CMD_P$3") (pintype "passive"))
    )
    (net (code "94") (name "/SDIO_D0") (class "Default")
      (node (ref "RN4") (pin "8") (pinfunction "8_8") (pintype "passive"))
      (node (ref "U1") (pin "G14") (pinfunction "PC8/TIM8_CH3/SDIO_D0/TIM3_CH3/USART6_CK/DCMI_D2_G14") (pintype "passive"))
      (node (ref "X2") (pin "P$7") (pinfunction "DAT0_P$7") (pintype "passive"))
    )
    (net (code "95") (name "/SDIO_D1") (class "Default")
      (node (ref "RN4") (pin "7") (pinfunction "7_7") (pintype "passive"))
      (node (ref "U1") (pin "F14") (pinfunction "PC9/I2S_CKIN/MCO2/TIM8_CH4/SDIO_D1/I2C3_SDA/DCMI_D3/TIM3_CH4_F14") (pintype "passive"))
      (node (ref "X2") (pin "P$8") (pinfunction "DAT1_P$8") (pintype "passive"))
    )
    (net (code "96") (name "/SDIO_D2") (class "Default")
      (node (ref "RN4") (pin "6") (pinfunction "6_6") (pintype "passive"))
      (node (ref "U1") (pin "B14") (pinfunction "PC10/SPI3_SCK/I2S3_CK/UART4_TX/SDIO_D2/DCMI_D8/USART3_TX_B14") (pintype "passive"))
      (node (ref "X2") (pin "P$1") (pinfunction "DAT2_P$1") (pintype "passive"))
    )
    (net (code "97") (name "/SDIO_D3") (class "Default")
      (node (ref "RN4") (pin "5") (pinfunction "5_5") (pintype "passive"))
      (node (ref "U1") (pin "B13") (pinfunction "PC11/UART4_RX/SPI3_MISO/SDIO_D3/DCMI_D4_B13") (pintype "passive"))
      (node (ref "X2") (pin "P$2") (pinfunction "DAT3/CD_P$2") (pintype "passive"))
    )
    (net (code "98") (name "/SD_CD") (class "Default")
      (node (ref "R10") (pin "2") (pinfunction "2_2") (pintype "passive"))
      (node (ref "U1") (pin "J14") (pinfunction "PG7/FSMC_INT3/DCMI_D13_J14") (pintype "passive"))
      (node (ref "X2") (pin "CD$1") (pinfunction "CD_CD$1") (pintype "power_in"))
    )
    (net (code "99") (name "/SPI2_MISO") (class "Default")
      (node (ref "JP1") (pin "2") (pinfunction "2_2") (pintype "passive"))
      (node (ref "U1") (pin "R14") (pinfunction "PB14/SPI2_MISO/TIM1_CH2N/TIM12_CH1/OTG_HS_DM/USART3_RTS/TIM8_CH2N_R14") (pintype "passive"))
    )
    (net (code "100") (name "/SPI2_MOSI") (class "Default")
      (node (ref "JP1") (pin "1") (pinfunction "1_1") (pintype "passive"))
      (node (ref "U1") (pin "R15") (pinfunction "PB15/SPI2_MOSI/I2S2_SD/TIM1_CH3N/TIM8_CH3N/TIM12_CH2/OTG_HS_DP_R15") (pintype "passive"))
    )
    (net (code "101") (name "/SPI2_NSS") (class "Default")
      (node (ref "JP1") (pin "4") (pinfunction "4_4") (pintype "passive"))
      (node (ref "U1") (pin "P12") (pinfunction "PB12/SPI2_NSS/I2S2_WS/I2C2_SMBA/USART3_CK/TIM1_BKIN/CAN2_RX_P12") (pintype "passive"))
    )
    (net (code "102") (name "/SPI2_SCLK") (class "Default")
      (node (ref "JP1") (pin "3") (pinfunction "3_3") (pintype "passive"))
      (node (ref "U1") (pin "P13") (pinfunction "PB13/SPI2_SCK/I2S2_CK/USART3_CTS/TIM1_CH1N/CAN2_TX/OTG_HS_ULPI_D6_P13") (pintype "passive"))
    )
    (net (code "103") (name "/SPI3_MISO") (class "Default")
      (node (ref "U1") (pin "A9") (pinfunction "PB4/NJTRST/TIM3_CH1/SPI1_MISO/SPI3_MISO/I2S3EXT_SD_A9") (pintype "passive"))
      (node (ref "X3") (pin "15") (pinfunction "15_15") (pintype "passive"))
    )
    (net (code "104") (name "/SPI3_MOSI") (class "Default")
      (node (ref "U1") (pin "A6") (pinfunction "PB5/TIM3_CH2/SPI1_MOSI/SPI3_MOSI/I2S3_SD/DCMI_D10/FMC_SDCKE1_A6") (pintype "passive"))
      (node (ref "X3") (pin "17") (pinfunction "17_17") (pintype "passive"))
    )
    (net (code "105") (name "/SPI3_SCLK{slash}TRACESWO") (class "Default")
      (node (ref "JP3") (pin "1") (pinfunction "1_1") (pintype "passive"))
      (node (ref "U1") (pin "A10") (pinfunction "PB3/JTDO/TRACESWO/SPI3_SCK/I2S3_CK/TIM2_CH2/SPI1_SCK_A10") (pintype "passive"))
      (node (ref "X3") (pin "13") (pinfunction "13_13") (pintype "passive"))
    )
    (net (code "106") (name "/SPI3_SSEL") (class "Default")
      (node (ref "U1") (pin "A13") (pinfunction "PA15/JTDI/SPI3_NSS/I2S3_WS/TIM2_CH1_ETR/SPI1_NSS_A13") (pintype "passive"))
      (node (ref "X3") (pin "11") (pinfunction "11_11") (pintype "passive"))
    )
    (net (code "107") (name "/SW") (class "Default")
      (node (ref "L1") (pin "1") (pinfunction "1_1") (pintype "passive"))
      (node (ref "U8") (pin "5") (pinfunction "SW_5") (pintype "power_in"))
    )
    (net (code "108") (name "/SWCLK") (class "Default")
      (node (ref "JP3") (pin "2") (pinfunction "2_2") (pintype "passive"))
      (node (ref "U1") (pin "A14") (pinfunction "PA14/JTCK-SWCLK_A14") (pintype "passive"))
    )
    (net (code "109") (name "/SWDIO") (class "Default")
      (node (ref "JP3") (pin "3") (pinfunction "3_3") (pintype "passive"))
      (node (ref "U1") (pin "A15") (pinfunction "PA13/JTMS-SWDIO_A15") (pintype "passive"))
    )
    (net (code "110") (name "/TIM4_CH1") (class "Default")
      (node (ref "JP2") (pin "6") (pinfunction "6_6") (pintype "passive"))
      (node (ref "U1") (pin "N13") (pinfunction "PD12/FMC_A17/TIM4_CH1/USART3_RTS_N13") (pintype "passive"))
    )
    (net (code "111") (name "/TIM4_CH2") (class "Default")
      (node (ref "JP2") (pin "5") (pinfunction "5_5") (pintype "passive"))
      (node (ref "U1") (pin "M15") (pinfunction "PD13/FMC_A18/TIM4_CH2_M15") (pintype "passive"))
    )
    (net (code "112") (name "/VCAP1") (class "Default")
      (node (ref "C12") (pin "1") (pinfunction "1_1") (pintype "passive"))
      (node (ref "U1") (pin "M10") (pinfunction "VCAP1_M10") (pintype "passive"))
    )
    (net (code "113") (name "/VCAP2") (class "Default")
      (node (ref "C11") (pin "1") (pinfunction "1_1") (pintype "passive"))
      (node (ref "U1") (pin "F13") (pinfunction "VCAP2_F13") (pintype "passive"))
    )
    (net (code "114") (name "GND") (class "Default")
      (node (ref "C1") (pin "1") (pinfunction "1_1") (pintype "passive"))
      (node (ref "C10") (pin "1") (pinfunction "1_1") (pintype "passive"))
      (node (ref "C11") (pin "2") (pinfunction "2_2") (pintype "passive"))
      (node (ref "C12") (pin "2") (pinfunction "2_2") (pintype "passive"))
      (node (ref "C13") (pin "2") (pinfunction "2_2") (pintype "passive"))
      (node (ref "C14") (pin "2") (pinfunction "2_2") (pintype "passive"))
      (node (ref "C15") (pin "2") (pinfunction "2_2") (pintype "passive"))
      (node (ref "C16") (pin "C") (pinfunction "-_C") (pintype "passive"))
      (node (ref "C17") (pin "2") (pinfunction "2_2") (pintype "passive"))
      (node (ref "C18") (pin "2") (pinfunction "2_2") (pintype "passive"))
      (node (ref "C19") (pin "2") (pinfunction "2_2") (pintype "passive"))
      (node (ref "C2") (pin "1") (pinfunction "1_1") (pintype "passive"))
      (node (ref "C20") (pin "2") (pinfunction "2_2") (pintype "passive"))
      (node (ref "C21") (pin "2") (pinfunction "2_2") (pintype "passive"))
      (node (ref "C22") (pin "2") (pinfunction "2_2") (pintype "passive"))
      (node (ref "C23") (pin "2") (pinfunction "2_2") (pintype "passive"))
      (node (ref "C24") (pin "2") (pinfunction "2_2") (pintype "passive"))
      (node (ref "C25") (pin "2") (pinfunction "2_2") (pintype "passive"))
      (node (ref "C26") (pin "2") (pinfunction "2_2") (pintype "passive"))
      (node (ref "C27") (pin "2") (pinfunction "2_2") (pintype "passive"))
      (node (ref "C28") (pin "2") (pinfunction "2_2") (pintype "passive"))
      (node (ref "C29") (pin "2") (pinfunction "2_2") (pintype "passive"))
      (node (ref "C3") (pin "1") (pinfunction "1_1") (pintype "passive"))
      (node (ref "C30") (pin "2") (pinfunction "2_2") (pintype "passive"))
      (node (ref "C4") (pin "1") (pinfunction "1_1") (pintype "passive"))
      (node (ref "C5") (pin "1") (pinfunction "1_1") (pintype "passive"))
      (node (ref "C6") (pin "C") (pinfunction "-_C") (pintype "passive"))
      (node (ref "C7") (pin "C") (pinfunction "-_C") (pintype "passive"))
      (node (ref "C8") (pin "2") (pinfunction "2_2") (pintype "passive"))
      (node (ref "C9") (pin "1") (pinfunction "1_1") (pintype "passive"))
      (node (ref "JP2") (pin "8") (pinfunction "8_8") (pintype "passive"))
      (node (ref "JP3") (pin "6") (pinfunction "6_6") (pintype "passive"))
      (node (ref "Q1") (pin "2") (pinfunction "S_2") (pintype "passive"))
      (node (ref "R1") (pin "1") (pinfunction "1_1") (pintype "passive"))
      (node (ref "R12") (pin "1") (pinfunction "1_1") (pintype "passive"))
      (node (ref "R3") (pin "1") (pinfunction "1_1") (pintype "passive"))
      (node (ref "R4") (pin "1") (pinfunction "1_1") (pintype "passive"))
      (node (ref "U1") (pin "D5") (pinfunction "VSS_D5") (pintype "passive"))
      (node (ref "U1") (pin "D7") (pinfunction "VSS_D7") (pintype "passive"))
      (node (ref "U1") (pin "D8") (pinfunction "VSS_D8") (pintype "passive"))
      (node (ref "U1") (pin "D9") (pinfunction "VSS_D9") (pintype "passive"))
      (node (ref "U1") (pin "F10") (pinfunction "VSS_F10") (pintype "passive"))
      (node (ref "U1") (pin "F12") (pinfunction "VSS_F12") (pintype "passive"))
      (node (ref "U1") (pin "F2") (pinfunction "VSS_F2") (pintype "passive"))
      (node (ref "U1") (pin "F6") (pinfunction "VSS_F6") (pintype "passive"))
      (node (ref "U1") (pin "F7") (pinfunction "VSS_F7") (pintype "passive"))
      (node (ref "U1") (pin "F8") (pinfunction "VSS_F8") (pintype "passive"))
      (node (ref "U1") (pin "F9") (pinfunction "VSS_F9") (pintype "passive"))
      (node (ref "U1") (pin "G10") (pinfunction "VSS_G10") (pintype "passive"))
      (node (ref "U1") (pin "G12") (pinfunction "VSS_G12") (pintype "passive"))
      (node (ref "U1") (pin "G2") (pinfunction "VSS_G2") (pintype "passive"))
      (node (ref "U1") (pin "G6") (pinfunction "VSS_G6") (pintype "passive"))
      (node (ref "U1") (pin "G7") (pinfunction "VSS_G7") (pintype "passive"))
      (node (ref "U1") (pin "G8") (pinfunction "VSS_G8") (pintype "passive"))
      (node (ref "U1") (pin "G9") (pinfunction "VSS_G9") (pintype "passive"))
      (node (ref "U1") (pin "H10") (pinfunction "VSS_H10") (pintype "passive"))
      (node (ref "U1") (pin "H12") (pinfunction "VSS_H12") (pintype "passive"))
      (node (ref "U1") (pin "H6") (pinfunction "VSS_H6") (pintype "passive"))
      (node (ref "U1") (pin "H7") (pinfunction "VSS_H7") (pintype "passive"))
      (node (ref "U1") (pin "H8") (pinfunction "VSS_H8") (pintype "passive"))
      (node (ref "U1") (pin "H9") (pinfunction "VSS_H9") (pintype "passive"))
      (node (ref "U1") (pin "J10") (pinfunction "VSS_J10") (pintype "passive"))
      (node (ref "U1") (pin "J6") (pinfunction "VSS_J6") (pintype "passive"))
      (node (ref "U1") (pin "J7") (pinfunction "VSS_J7") (pintype "passive"))
      (node (ref "U1") (pin "J8") (pinfunction "VSS_J8") (pintype "passive"))
      (node (ref "U1") (pin "J9") (pinfunction "VSS_J9") (pintype "passive"))
      (node (ref "U1") (pin "K10") (pinfunction "VSS_K10") (pintype "passive"))
      (node (ref "U1") (pin "K6") (pinfunction "VSS_K6") (pintype "passive"))
      (node (ref "U1") (pin "K7") (pinfunction "VSS_K7") (pintype "passive"))
      (node (ref "U1") (pin "K8") (pinfunction "VSS_K8") (pintype "passive"))
      (node (ref "U1") (pin "K9") (pinfunction "VSS_K9") (pintype "passive"))
      (node (ref "U1") (pin "L4") (pinfunction "VSS_L4") (pintype "passive"))
      (node (ref "U1") (pin "M1") (pinfunction "VSSA_M1") (pintype "passive"))
      (node (ref "U1") (pin "M8") (pinfunction "VSS_M8") (pintype "passive"))
      (node (ref "U1") (pin "M9") (pinfunction "VSS_M9") (pintype "passive"))
      (node (ref "U1") (pin "N1") (pinfunction "VREF-_N1") (pintype "passive"))
      (node (ref "U2") (pin "A3") (pinfunction "VSS_A3") (pintype "passive"))
      (node (ref "U2") (pin "B3") (pinfunction "VSSQ_B3") (pintype "passive"))
      (node (ref "U2") (pin "B8") (pinfunction "VSSQ_B8") (pintype "passive"))
      (node (ref "U2") (pin "C1") (pinfunction "VSSQ_C1") (pintype "passive"))
      (node (ref "U2") (pin "D1") (pinfunction "VSSQ_D1") (pintype "passive"))
      (node (ref "U2") (pin "E9") (pinfunction "VSSQ_E9") (pintype "passive"))
      (node (ref "U2") (pin "F1") (pinfunction "VSS_F1") (pintype "passive"))
      (node (ref "U2") (pin "L3") (pinfunction "VSS_L3") (pintype "passive"))
      (node (ref "U2") (pin "L9") (pinfunction "VSSQ_L9") (pintype "passive"))
      (node (ref "U2") (pin "M1") (pinfunction "VSSQ_M1") (pintype "passive"))
      (node (ref "U2") (pin "N1") (pinfunction "VSSQ_N1") (pintype "passive"))
      (node (ref "U2") (pin "P3") (pinfunction "VSSQ_P3") (pintype "passive"))
      (node (ref "U2") (pin "P8") (pinfunction "VSSQ_P8") (pintype "passive"))
      (node (ref "U2") (pin "R3") (pinfunction "VSS_R3") (pintype "passive"))
      (node (ref "U3") (pin "2") (pinfunction "VSS_2") (pintype "passive"))
      (node (ref "U5") (pin "2") (pinfunction "2_2") (pintype "passive"))
      (node (ref "U6") (pin "4") (pinfunction "GND_4") (pintype "passive"))
      (node (ref "U8") (pin "2") (pinfunction "GND_2") (pintype "power_in"))
      (node (ref "X1") (pin "5") (pinfunction "GND_5") (pintype "power_in"))
      (node (ref "X1") (pin "S") (pinfunction "SLD_S") (pintype "passive"))
      (node (ref "X2") (pin "CD$2") (pinfunction "CD_POL_CD$2") (pintype "power_in"))
      (node (ref "X2") (pin "G") (pinfunction "SHD_G") (pintype "power_in"))
      (node (ref "X2") (pin "P$6") (pinfunction "VSS_P$6") (pintype "power_in"))
      (node (ref "X3") (pin "19") (pinfunction "19_19") (pintype "passive"))
      (node (ref "X3") (pin "27") (pinfunction "27_27") (pintype "passive"))
      (node (ref "X3") (pin "5") (pinfunction "5_5") (pintype "passive"))
      (node (ref "X4") (pin "2") (pinfunction "1_2") (pintype "passive"))
      (node (ref "Y2") (pin "2") (pinfunction "OSC2_2") (pintype "passive"))
      (node (ref "Y2") (pin "4") (pinfunction "OSC4_4") (pintype "passive"))
    )
    (net (code "115") (name "Net-(LED1-BLU)") (class "Default")
      (node (ref "LED1") (pin "B") (pinfunction "BLU_B") (pintype "passive"))
      (node (ref "RN3") (pin "8") (pinfunction "8_8") (pintype "passive"))
    )
    (net (code "116") (name "Net-(LED1-GRN)") (class "Default")
      (node (ref "LED1") (pin "G") (pinfunction "GRN_G") (pintype "passive"))
      (node (ref "RN3") (pin "7") (pinfunction "7_7") (pintype "passive"))
    )
    (net (code "117") (name "Net-(LED1-RED)") (class "Default")
      (node (ref "LED1") (pin "R") (pinfunction "RED_R") (pintype "passive"))
      (node (ref "RN3") (pin "6") (pinfunction "6_6") (pintype "passive"))
    )
    (net (code "118") (name "Net-(LED2-PadC)") (class "Default")
      (node (ref "LED2") (pin "C") (pinfunction "C_C") (pintype "passive"))
      (node (ref "LED3") (pin "A") (pinfunction "A_A") (pintype "passive"))
    )
    (net (code "119") (name "Net-(LED3-PadC)") (class "Default")
      (node (ref "LED3") (pin "C") (pinfunction "C_C") (pintype "passive"))
      (node (ref "R5") (pin "2") (pinfunction "2_2") (pintype "passive"))
    )
    (net (code "120") (name "Net-(Q1-D)") (class "Default")
      (node (ref "Q1") (pin "3") (pinfunction "D_3") (pintype "passive"))
      (node (ref "R5") (pin "1") (pinfunction "1_1") (pintype "passive"))
    )
    (net (code "121") (name "Net-(Q1-G)") (class "Default")
      (node (ref "Q1") (pin "1") (pinfunction "G_1") (pintype "passive"))
      (node (ref "R4") (pin "2") (pinfunction "2_2") (pintype "passive"))
      (node (ref "RN3") (pin "5") (pinfunction "5_5") (pintype "passive"))
    )
    (net (code "122") (name "Net-(U1A-PA9{slash}TIM1_CH2{slash}I2C3_SMBA{slash}USART1_TX{slash}DCMI_D0{slash}OTG_FS_VBUS)") (class "Default")
      (node (ref "R9") (pin "1") (pinfunction "1_1") (pintype "passive"))
      (node (ref "U1") (pin "E15") (pinfunction "PA9/TIM1_CH2/I2C3_SMBA/USART1_TX/DCMI_D0/OTG_FS_VBUS_E15") (pintype "passive"))
    )
    (net (code "123") (name "Net-(U1A-PH0{slash}OSC_IN)") (class "Default")
      (node (ref "C10") (pin "2") (pinfunction "2_2") (pintype "passive"))
      (node (ref "U1") (pin "G1") (pinfunction "PH0/OSC_IN_G1") (pintype "passive"))
      (node (ref "Y2") (pin "3") (pinfunction "OSC3_3") (pintype "passive"))
    )
    (net (code "124") (name "Net-(U1A-PH1{slash}OSC_OUT)") (class "Default")
      (node (ref "C9") (pin "2") (pinfunction "2_2") (pintype "passive"))
      (node (ref "U1") (pin "H1") (pinfunction "PH1/OSC_OUT_H1") (pintype "passive"))
      (node (ref "Y2") (pin "1") (pinfunction "OSC1_1") (pintype "passive"))
    )
    (net (code "125") (name "Net-(U1B-VDDA)") (class "Default")
      (node (ref "C13") (pin "1") (pinfunction "1_1") (pintype "passive"))
      (node (ref "C14") (pin "1") (pinfunction "1_1") (pintype "passive"))
      (node (ref "L2") (pin "1") (pinfunction "1_1") (pintype "passive"))
      (node (ref "U1") (pin "P1") (pinfunction "VREF+_P1") (pintype "passive"))
      (node (ref "U1") (pin "R1") (pinfunction "VDDA_R1") (pintype "passive"))
    )
    (net (code "126") (name "Net-(U8-VOUT{slash}FB)") (class "Default")
      (node (ref "R2") (pin "1") (pinfunction "1_1") (pintype "passive"))
      (node (ref "R3") (pin "2") (pinfunction "2_2") (pintype "passive"))
      (node (ref "U8") (pin "4") (pinfunction "VOUT/FB_4") (pintype "passive"))
    )
    (net (code "127") (name "Net-(X1-D+)") (class "Default")
      (node (ref "U5") (pin "3") (pinfunction "3_3") (pintype "passive"))
      (node (ref "X1") (pin "3") (pinfunction "D+_3") (pintype "passive"))
    )
    (net (code "128") (name "Net-(X1-D-)") (class "Default")
      (node (ref "U5") (pin "1") (pinfunction "1_1") (pintype "passive"))
      (node (ref "X1") (pin "2") (pinfunction "D-_2") (pintype "passive"))
    )
    (net (code "129") (name "RAW") (class "Default")
      (node (ref "C2") (pin "2") (pinfunction "2_2") (pintype "passive"))
      (node (ref "D1") (pin "1") (pinfunction "C_1") (pintype "passive"))
      (node (ref "Q2") (pin "2") (pinfunction "S_2") (pintype "passive"))
      (node (ref "U8") (pin "1") (pinfunction "VIN_1") (pintype "power_in"))
      (node (ref "U8") (pin "3") (pinfunction "EN_3") (pintype "passive"))
    )
    (net (code "130") (name "VBUS") (class "Default")
      (node (ref "C1") (pin "2") (pinfunction "2_2") (pintype "passive"))
      (node (ref "Q2") (pin "3") (pinfunction "D_3") (pintype "passive"))
      (node (ref "R9") (pin "2") (pinfunction "2_2") (pintype "passive"))
      (node (ref "U5") (pin "5") (pinfunction "5_5") (pintype "passive"))
      (node (ref "X1") (pin "1") (pinfunction "5V_1") (pintype "power_in"))
    )
    (net (code "131") (name "VCC") (class "Default")
      (node (ref "C16") (pin "A") (pinfunction "+_A") (pintype "passive"))
      (node (ref "C17") (pin "1") (pinfunction "1_1") (pintype "passive"))
      (node (ref "C18") (pin "1") (pinfunction "1_1") (pintype "passive"))
      (node (ref "C19") (pin "1") (pinfunction "1_1") (pintype "passive"))
      (node (ref "C20") (pin "1") (pinfunction "1_1") (pintype "passive"))
      (node (ref "C21") (pin "1") (pinfunction "1_1") (pintype "passive"))
      (node (ref "C22") (pin "1") (pinfunction "1_1") (pintype "passive"))
      (node (ref "C23") (pin "1") (pinfunction "1_1") (pintype "passive"))
      (node (ref "C24") (pin "1") (pinfunction "1_1") (pintype "passive"))
      (node (ref "C25") (pin "1") (pinfunction "1_1") (pintype "passive"))
      (node (ref "C26") (pin "1") (pinfunction "1_1") (pintype "passive"))
      (node (ref "C27") (pin "1") (pinfunction "1_1") (pintype "passive"))
      (node (ref "C28") (pin "1") (pinfunction "1_1") (pintype "passive"))
      (node (ref "C29") (pin "1") (pinfunction "1_1") (pintype "passive"))
      (node (ref "C3") (pin "2") (pinfunction "2_2") (pintype "passive"))
      (node (ref "C30") (pin "1") (pinfunction "1_1") (pintype "passive"))
      (node (ref "C4") (pin "2") (pinfunction "2_2") (pintype "passive"))
      (node (ref "C6") (pin "A") (pinfunction "+_A") (pintype "passive"))
      (node (ref "C7") (pin "A") (pinfunction "+_A") (pintype "passive"))
      (node (ref "C8") (pin "1") (pinfunction "1_1") (pintype "passive"))
      (node (ref "JP1") (pin "8") (pinfunction "8_8") (pintype "passive"))
      (node (ref "JP3") (pin "5") (pinfunction "5_5") (pintype "passive"))
      (node (ref "L1") (pin "2") (pinfunction "2_2") (pintype "passive"))
      (node (ref "L2") (pin "2") (pinfunction "2_2") (pintype "passive"))
      (node (ref "LED1") (pin "A") (pinfunction "A_A") (pintype "passive"))
      (node (ref "LED2") (pin "A") (pinfunction "A_A") (pintype "passive"))
      (node (ref "R10") (pin "1") (pinfunction "1_1") (pintype "passive"))
      (node (ref "R11") (pin "1") (pinfunction "1_1") (pintype "passive"))
      (node (ref "R13") (pin "2") (pinfunction "2_2") (pintype "passive"))
      (node (ref "R14") (pin "2") (pinfunction "2_2") (pintype "passive"))
      (node (ref "R15") (pin "2") (pinfunction "2_2") (pintype "passive"))
      (node (ref "R2") (pin "2") (pinfunction "2_2") (pintype "passive"))
      (node (ref "R6") (pin "1") (pinfunction "1_1") (pintype "passive"))
      (node (ref "R7") (pin "1") (pinfunction "1_1") (pintype "passive"))
      (node (ref "R8") (pin "1") (pinfunction "1_1") (pintype "passive"))
      (node (ref "RN4") (pin "1") (pinfunction "1_1") (pintype "passive"))
      (node (ref "RN4") (pin "2") (pinfunction "2_2") (pintype "passive"))
      (node (ref "RN4") (pin "3") (pinfunction "3_3") (pintype "passive"))
      (node (ref "RN4") (pin "4") (pinfunction "4_4") (pintype "passive"))
      (node (ref "U1") (pin "C1") (pinfunction "VBAT_C1") (pintype "passive"))
      (node (ref "U1") (pin "C5") (pinfunction "VDD_C5") (pintype "passive"))
      (node (ref "U1") (pin "C6") (pinfunction "PDR_ON_C6") (pintype "passive"))
      (node (ref "U1") (pin "C7") (pinfunction "VDD_C7") (pintype "passive"))
      (node (ref "U1") (pin "C8") (pinfunction "VDD_C8") (pintype "passive"))
      (node (ref "U1") (pin "C9") (pinfunction "VDD_C9") (pintype "passive"))
      (node (ref "U1") (pin "F3") (pinfunction "VDD_F3") (pintype "passive"))
      (node (ref "U1") (pin "G13") (pinfunction "VDD_G13") (pintype "passive"))
      (node (ref "U1") (pin "G3") (pinfunction "VDD_G3") (pintype "passive"))
      (node (ref "U1") (pin "H13") (pinfunction "VDD33USB_H13") (pintype "passive"))
      (node (ref "U1") (pin "J12") (pinfunction "VDD_J12") (pintype "passive"))
      (node (ref "U1") (pin "J13") (pinfunction "VDD_J13") (pintype "passive"))
      (node (ref "U1") (pin "K4") (pinfunction "VDD_K4") (pintype "passive"))
      (node (ref "U1") (pin "N10") (pinfunction "VDD_N10") (pintype "passive"))
      (node (ref "U1") (pin "N8") (pinfunction "VDD_N8") (pintype "passive"))
      (node (ref "U1") (pin "N9") (pinfunction "VDD_N9") (pintype "passive"))
      (node (ref "U2") (pin "A7") (pinfunction "VDD_A7") (pintype "passive"))
      (node (ref "U2") (pin "B2") (pinfunction "VDDQ_B2") (pintype "passive"))
      (node (ref "U2") (pin "B7") (pinfunction "VDDQ_B7") (pintype "passive"))
      (node (ref "U2") (pin "C9") (pinfunction "VDDQ_C9") (pintype "passive"))
      (node (ref "U2") (pin "D9") (pinfunction "VDDQ_D9") (pintype "passive"))
      (node (ref "U2") (pin "E1") (pinfunction "VDDQ_E1") (pintype "passive"))
      (node (ref "U2") (pin "F9") (pinfunction "VDD_F9") (pintype "passive"))
      (node (ref "U2") (pin "L1") (pinfunction "VDDQ_L1") (pintype "passive"))
      (node (ref "U2") (pin "L7") (pinfunction "VDD_L7") (pintype "passive"))
      (node (ref "U2") (pin "M9") (pinfunction "VDDQ_M9") (pintype "passive"))
      (node (ref "U2") (pin "N9") (pinfunction "VDDQ_N9") (pintype "passive"))
      (node (ref "U2") (pin "P2") (pinfunction "VDDQ_P2") (pintype "passive"))
      (node (ref "U2") (pin "P7") (pinfunction "VDDQ_P7") (pintype "passive"))
      (node (ref "U2") (pin "R7") (pinfunction "VDD_R7") (pintype "passive"))
      (node (ref "U3") (pin "1") (pinfunction "VIN_1") (pintype "passive"))
      (node (ref "U3") (pin "3") (pinfunction "CE_3") (pintype "passive"))
      (node (ref "U6") (pin "8") (pinfunction "VCC_8") (pintype "passive"))
      (node (ref "X2") (pin "P$4") (pinfunction "VDD_P$4") (pintype "power_in"))
      (node (ref "X3") (pin "10") (pinfunction "10_10") (pintype "passive"))
      (node (ref "X3") (pin "2") (pinfunction "2_2") (pintype "passive"))
      (node (ref "X3") (pin "20") (pinfunction "20_20") (pintype "passive"))
      (node (ref "X3") (pin "30") (pinfunction "30_30") (pintype "passive"))
      (node (ref "X3") (pin "36") (pinfunction "36_36") (pintype "passive"))
    )
    (net (code "132") (name "VDDA") (class "Default")
      (node (ref "C5") (pin "2") (pinfunction "2_2") (pintype "passive"))
      (node (ref "U3") (pin "5") (pinfunction "VOUT_5") (pintype "passive"))
      (node (ref "X3") (pin "4") (pinfunction "4_4") (pintype "passive"))
    )
    (net (code "133") (name "VIN") (class "Default")
      (node (ref "D1") (pin "2") (pinfunction "A_2") (pintype "passive"))
      (node (ref "JP2") (pin "7") (pinfunction "7_7") (pintype "passive"))
      (node (ref "Q2") (pin "1") (pinfunction "G_1") (pintype "passive"))
      (node (ref "R1") (pin "2") (pinfunction "2_2") (pintype "passive"))
      (node (ref "X4") (pin "1") (pinfunction "2_1") (pintype "passive"))
    )
    (net (code "134") (name "unconnected-(H1-MOUNT-PadB2)") (class "Default")
      (node (ref "H1") (pin "B2") (pinfunction "MOUNT_B2") (pintype "passive"))
      (node (ref "H1") (pin "8") (pinfunction "MOUNT_8") (pintype "passive"))
    )
    (net (code "135") (name "unconnected-(H2-MOUNT-PadB2)") (class "Default")
      (node (ref "H2") (pin "B2") (pinfunction "MOUNT_B2") (pintype "passive"))
      (node (ref "H2") (pin "8") (pinfunction "MOUNT_8") (pintype "passive"))
    )
    (net (code "136") (name "unconnected-(U1A-PA0{slash}USART2_CTS{slash}UART4_TX{slash}TIM2_CH1_ETR{slash}WKUP{slash}TIM5_CH1{slash}TIM8_ETR-PadN3)") (class "Default")
      (node (ref "U1") (pin "N3") (pinfunction "PA0/USART2_CTS/UART4_TX/TIM2_CH1_ETR/WKUP/TIM5_CH1/TIM8_ETR_N3") (pintype "passive+no_connect"))
    )
    (net (code "137") (name "unconnected-(U1A-PA1{slash}USART2_RTS{slash}UART4_RX{slash}TIM5_CH2{slash}TIM2_CH2-PadN2)") (class "Default")
      (node (ref "U1") (pin "N2") (pinfunction "PA1/USART2_RTS/UART4_RX/TIM5_CH2/TIM2_CH2_N2") (pintype "passive+no_connect"))
    )
    (net (code "138") (name "unconnected-(U1A-PA2{slash}USART2_TX{slash}TIM5_CH3{slash}TIM9_CH1{slash}TIM2_CH3{slash}ETH_MDIO-PadP2)") (class "Default")
      (node (ref "U1") (pin "P2") (pinfunction "PA2/USART2_TX/TIM5_CH3/TIM9_CH1/TIM2_CH3/ETH_MDIO_P2") (pintype "passive+no_connect"))
    )
    (net (code "139") (name "unconnected-(U1A-PA3{slash}USART2_RX{slash}TIM5_CH4{slash}TIM9_CH2{slash}TIM2_CH4{slash}OTG_HS_ULPI_D0-PadR2)") (class "Default")
      (node (ref "U1") (pin "R2") (pinfunction "PA3/USART2_RX/TIM5_CH4/TIM9_CH2/TIM2_CH4/OTG_HS_ULPI_D0_R2") (pintype "passive+no_connect"))
    )
    (net (code "140") (name "unconnected-(U1A-PB0{slash}TIM3_CH3{slash}TIM8_CH2N{slash}TIM1_CH2N{slash}OTG_HS_ULPI_D1{slash}ETH_MII_RXD2-PadR5)") (class "Default")
      (node (ref "U1") (pin "R5") (pinfunction "PB0/TIM3_CH3/TIM8_CH2N/TIM1_CH2N/OTG_HS_ULPI_D1/ETH_MII_RXD2_R5") (pintype "passive+no_connect"))
    )
    (net (code "141") (name "unconnected-(U1A-PB1{slash}TIM3_CH4{slash}TIM8_CH3N{slash}TIM1_CH3N{slash}OTG_HS_ULPI_D2{slash}ETH_MII_RXD3-PadR4)") (class "Default")
      (node (ref "U1") (pin "R4") (pinfunction "PB1/TIM3_CH4/TIM8_CH3N/TIM1_CH3N/OTG_HS_ULPI_D2/ETH_MII_RXD3_R4") (pintype "passive+no_connect"))
    )
    (net (code "142") (name "unconnected-(U1A-PB2{slash}BOOT1-PadM6)") (class "Default")
      (node (ref "U1") (pin "M6") (pinfunction "PB2/BOOT1_M6") (pintype "passive+no_connect"))
    )
    (net (code "143") (name "unconnected-(U1A-PC3{slash}SPI2_MOSI{slash}I2S2_SD{slash}OTG_HS_ULPI_NXT{slash}ETH_MII_TX_CLK{slash}FMC_SDCKE0-PadM5)") (class "Default")
      (node (ref "U1") (pin "M5") (pinfunction "PC3/SPI2_MOSI/I2S2_SD/OTG_HS_ULPI_NXT/ETH_MII_TX_CLK/FMC_SDCKE0_M5") (pintype "passive+no_connect"))
    )
    (net (code "144") (name "unconnected-(U1A-PC13{slash}TAMP_1-PadD1)") (class "Default")
      (node (ref "U1") (pin "D1") (pinfunction "PC13/TAMP_1_D1") (pintype "passive+no_connect"))
    )
    (net (code "145") (name "unconnected-(U1A-PC14{slash}OSC32_IN-PadE1)") (class "Default")
      (node (ref "U1") (pin "E1") (pinfunction "PC14/OSC32_IN_E1") (pintype "passive+no_connect"))
    )
    (net (code "146") (name "unconnected-(U1A-PC15{slash}OSC32_OUT-PadF1)") (class "Default")
      (node (ref "U1") (pin "F1") (pinfunction "PC15/OSC32_OUT_F1") (pintype "passive+no_connect"))
    )
    (net (code "147") (name "unconnected-(U1A-PD3{slash}SPI2_SCK{slash}I2S2_CK{slash}USART2_CTS{slash}FMC_CLK{slash}DCMI_D5-PadD11)") (class "Default")
      (node (ref "U1") (pin "D11") (pinfunction "PD3/SPI2_SCK/I2S2_CK/USART2_CTS/FMC_CLK/DCMI_D5_D11") (pintype "passive+no_connect"))
    )
    (net (code "148") (name "unconnected-(U1A-PD4{slash}USART2_RTS{slash}FMC_NOE-PadD10)") (class "Default")
      (node (ref "U1") (pin "D10") (pinfunction "PD4/USART2_RTS/FMC_NOE_D10") (pintype "passive+no_connect"))
    )
    (net (code "149") (name "unconnected-(U1A-PD5{slash}USART2_TX{slash}FMC_NWE-PadC11)") (class "Default")
      (node (ref "U1") (pin "C11") (pinfunction "PD5/USART2_TX/FMC_NWE_C11") (pintype "passive+no_connect"))
    )
    (net (code "150") (name "unconnected-(U1A-PD6{slash}SPI3_MOSI{slash}I2S3_SD{slash}USART2_RX{slash}FMC_NWAIT{slash}DCMI_D10-PadB11)") (class "Default")
      (node (ref "U1") (pin "B11") (pinfunction "PD6/SPI3_MOSI/I2S3_SD/USART2_RX/FMC_NWAIT/DCMI_D10_B11") (pintype "passive+no_connect"))
    )
    (net (code "151") (name "unconnected-(U1A-PD11{slash}FMC_A16{slash}USART3_CTS-PadN14)") (class "Default")
      (node (ref "U1") (pin "N14") (pinfunction "PD11/FMC_A16/USART3_CTS_N14") (pintype "passive+no_connect"))
    )
    (net (code "152") (name "unconnected-(U1A-PE3{slash}TRACED0{slash}FSMC_A19-PadA1)") (class "Default")
      (node (ref "U1") (pin "A1") (pinfunction "PE3/TRACED0/FSMC_A19_A1") (pintype "passive+no_connect"))
    )
    (net (code "153") (name "unconnected-(U1A-PG2{slash}FMC_A12-PadL15)") (class "Default")
      (node (ref "U1") (pin "L15") (pinfunction "PG2/FMC_A12_L15") (pintype "passive+no_connect"))
    )
    (net (code "154") (name "unconnected-(U1A-PG9{slash}USART6_RX{slash}FMC_NE2{slash}FMC_NCE3{slash}DCMI_VSYNC-PadC10)") (class "Default")
      (node (ref "U1") (pin "C10") (pinfunction "PG9/USART6_RX/FMC_NE2/FMC_NCE3/DCMI_VSYNC_C10") (pintype "passive+no_connect"))
    )
    (net (code "155") (name "unconnected-(U1A-PG12{slash}SPI6_MISO{slash}USART6_RTS{slash}LCD_B4{slash}FMC_NE4{slash}LCD_B1-PadB8)") (class "Default")
      (node (ref "U1") (pin "B8") (pinfunction "PG12/SPI6_MISO/USART6_RTS/LCD_B4/FMC_NE4/LCD_B1_B8") (pintype "passive+no_connect"))
    )
    (net (code "156") (name "unconnected-(U1A-PG13{slash}SPI6_SCK{slash}USART6_CTS{slash}ETH_MII_TXD0{slash}ETH_RMII_TXD0{slash}FMC_A24-PadA8)") (class "Default")
      (node (ref "U1") (pin "A8") (pinfunction "PG13/SPI6_SCK/USART6_CTS/ETH_MII_TXD0/ETH_RMII_TXD0/FMC_A24_A8") (pintype "passive+no_connect"))
    )
    (net (code "157") (name "unconnected-(U1A-PG14{slash}SPI6_MOSI{slash}USART6_TX{slash}ETH_MII_TXD1{slash}ETH_RMII_TXD1{slash}FMC_A25-PadA7)") (class "Default")
      (node (ref "U1") (pin "A7") (pinfunction "PG14/SPI6_MOSI/USART6_TX/ETH_MII_TXD1/ETH_RMII_TXD1/FMC_A25_A7") (pintype "passive+no_connect"))
    )
    (net (code "158") (name "unconnected-(U1A-PH2{slash}FMC_SDCKE0-PadF4)") (class "Default")
      (node (ref "U1") (pin "F4") (pinfunction "PH2/FMC_SDCKE0_F4") (pintype "passive+no_connect"))
    )
    (net (code "159") (name "unconnected-(U1A-PH3{slash}FMC_SDNE0-PadG4)") (class "Default")
      (node (ref "U1") (pin "G4") (pinfunction "PH3/FMC_SDNE0_G4") (pintype "passive+no_connect"))
    )
    (net (code "160") (name "unconnected-(U1A-PH4{slash}I2C2_SCL-PadH4)") (class "Default")
      (node (ref "U1") (pin "H4") (pinfunction "PH4/I2C2_SCL_H4") (pintype "passive+no_connect"))
    )
    (net (code "161") (name "unconnected-(U1A-PH5{slash}I2C2_SDA-PadJ4)") (class "Default")
      (node (ref "U1") (pin "J4") (pinfunction "PH5/I2C2_SDA_J4") (pintype "passive+no_connect"))
    )
    (net (code "162") (name "unconnected-(U1A-PH6-PadM11)") (class "Default")
      (node (ref "U1") (pin "M11") (pinfunction "PH6_M11") (pintype "passive+no_connect"))
    )
    (net (code "163") (name "unconnected-(U1A-PH7-PadN12)") (class "Default")
      (node (ref "U1") (pin "N12") (pinfunction "PH7_N12") (pintype "passive+no_connect"))
    )
    (net (code "164") (name "unconnected-(U1A-PI8-PadD2)") (class "Default")
      (node (ref "U1") (pin "D2") (pinfunction "PI8_D2") (pintype "passive+no_connect"))
    )
    (net (code "165") (name "unconnected-(U1A-PI11-PadE4)") (class "Default")
      (node (ref "U1") (pin "E4") (pinfunction "PI11_E4") (pintype "passive+no_connect"))
    )
    (net (code "166") (name "unconnected-(U2-NC-PadE3)") (class "Default")
      (node (ref "U2") (pin "E3") (pinfunction "NC_E3") (pintype "passive+no_connect"))
    )
    (net (code "167") (name "unconnected-(U2-NC-PadE7)") (class "Default")
      (node (ref "U2") (pin "E7") (pinfunction "NC_E7") (pintype "passive+no_connect"))
    )
    (net (code "168") (name "unconnected-(U2-NC-PadH3)") (class "Default")
      (node (ref "U2") (pin "H3") (pinfunction "NC_H3") (pintype "passive+no_connect"))
    )
    (net (code "169") (name "unconnected-(U2-NC-PadH7)") (class "Default")
      (node (ref "U2") (pin "H7") (pinfunction "NC_H7") (pintype "passive+no_connect"))
    )
    (net (code "170") (name "unconnected-(U2-NC-PadK2)") (class "Default")
      (node (ref "U2") (pin "K2") (pinfunction "NC_K2") (pintype "passive+no_connect"))
    )
    (net (code "171") (name "unconnected-(U2-NC-PadK3)") (class "Default")
      (node (ref "U2") (pin "K3") (pinfunction "NC_K3") (pintype "passive+no_connect"))
    )
    (net (code "172") (name "unconnected-(U3-NC-Pad4)") (class "Default")
      (node (ref "U3") (pin "4") (pinfunction "NC_4") (pintype "passive+no_connect"))
    )
    (net (code "173") (name "unconnected-(X1-ID-Pad4)") (class "Default")
      (node (ref "X1") (pin "4") (pinfunction "ID_4") (pintype "passive+no_connect"))
    )
    (net (code "174") (name "unconnected-(X3-Pad1)") (class "Default")
      (node (ref "X3") (pin "1") (pinfunction "1_1") (pintype "passive"))
    )
    (net (code "175") (name "unconnected-(X3-Pad3)") (class "Default")
      (node (ref "X3") (pin "3") (pinfunction "3_3") (pintype "passive"))
    )
    (net (code "176") (name "unconnected-(X3-Pad6)") (class "Default")
      (node (ref "X3") (pin "6") (pinfunction "6_6") (pintype "passive"))
    )
    (net (code "177") (name "unconnected-(X3-Pad7)") (class "Default")
      (node (ref "X3") (pin "7") (pinfunction "7_7") (pintype "passive"))
    )
    (net (code "178") (name "unconnected-(X3-Pad8)") (class "Default")
      (node (ref "X3") (pin "8") (pinfunction "8_8") (pintype "passive"))
    )
    (net (code "179") (name "unconnected-(X3-Pad9)") (class "Default")
      (node (ref "X3") (pin "9") (pinfunction "9_9") (pintype "passive"))
    )
  )
)
